# Sch_ECGAcquisitionSystem.net
KiCad netlist of a schematic drawn in Altium Designer
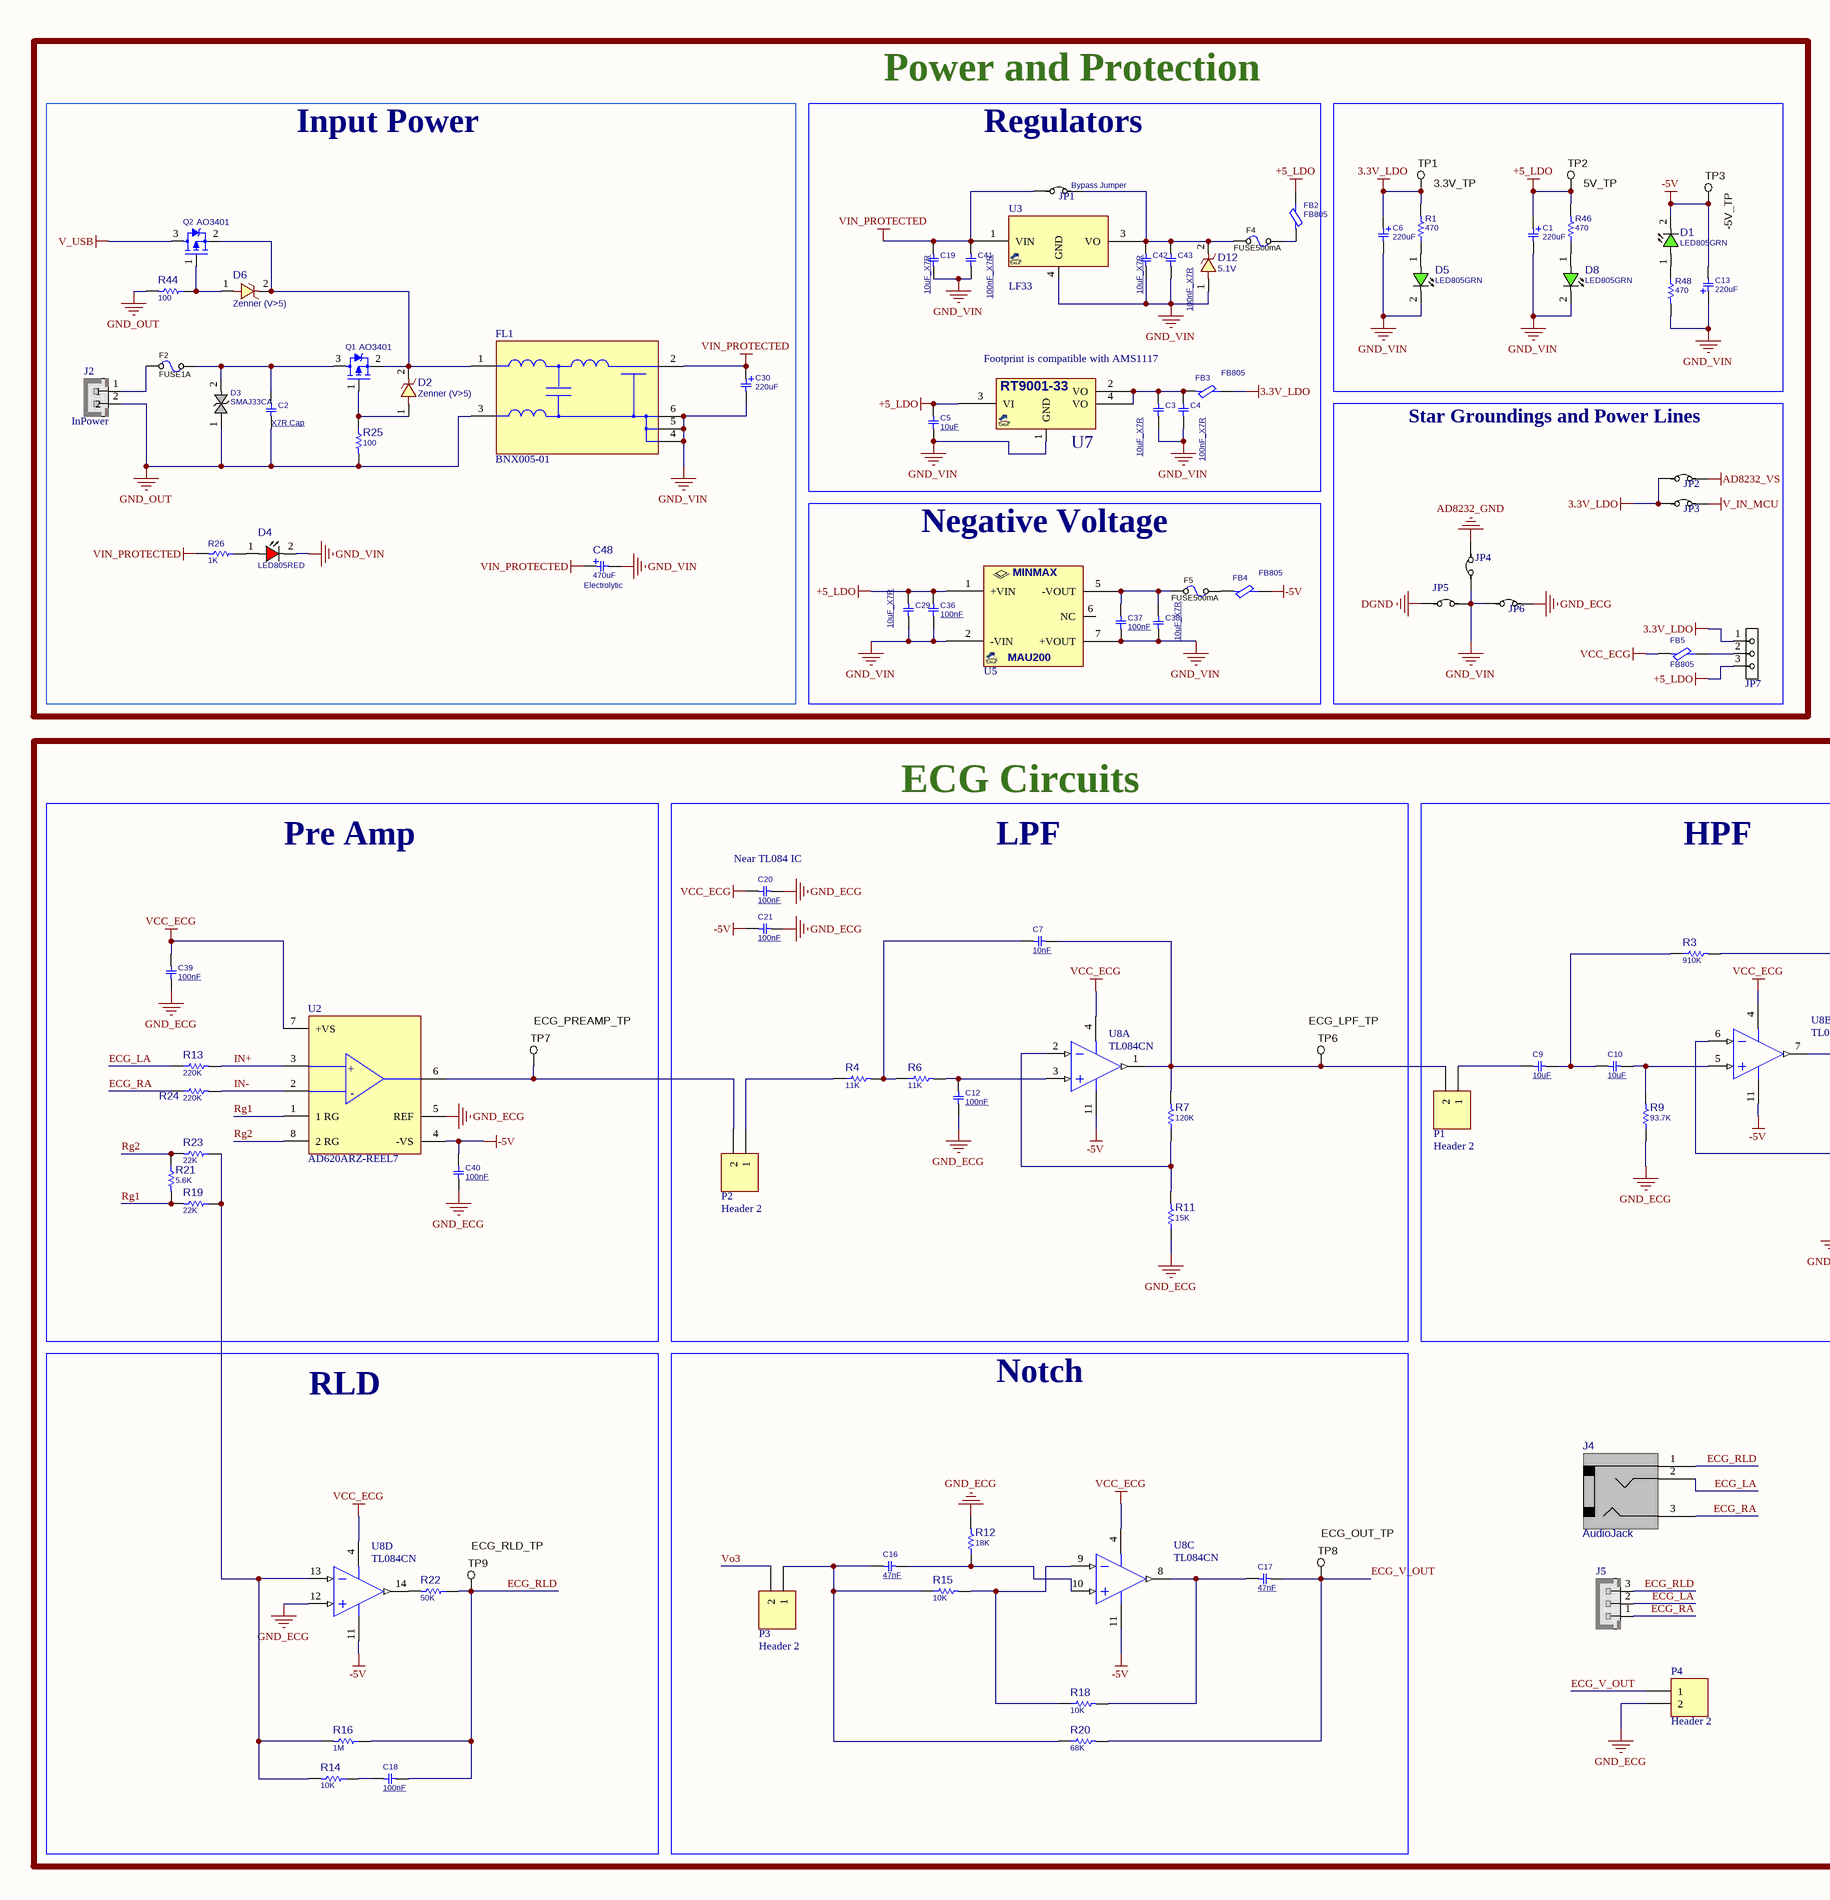
[diagram p0: Sch_ECGAcquisitionSystem.SchDoc, left]
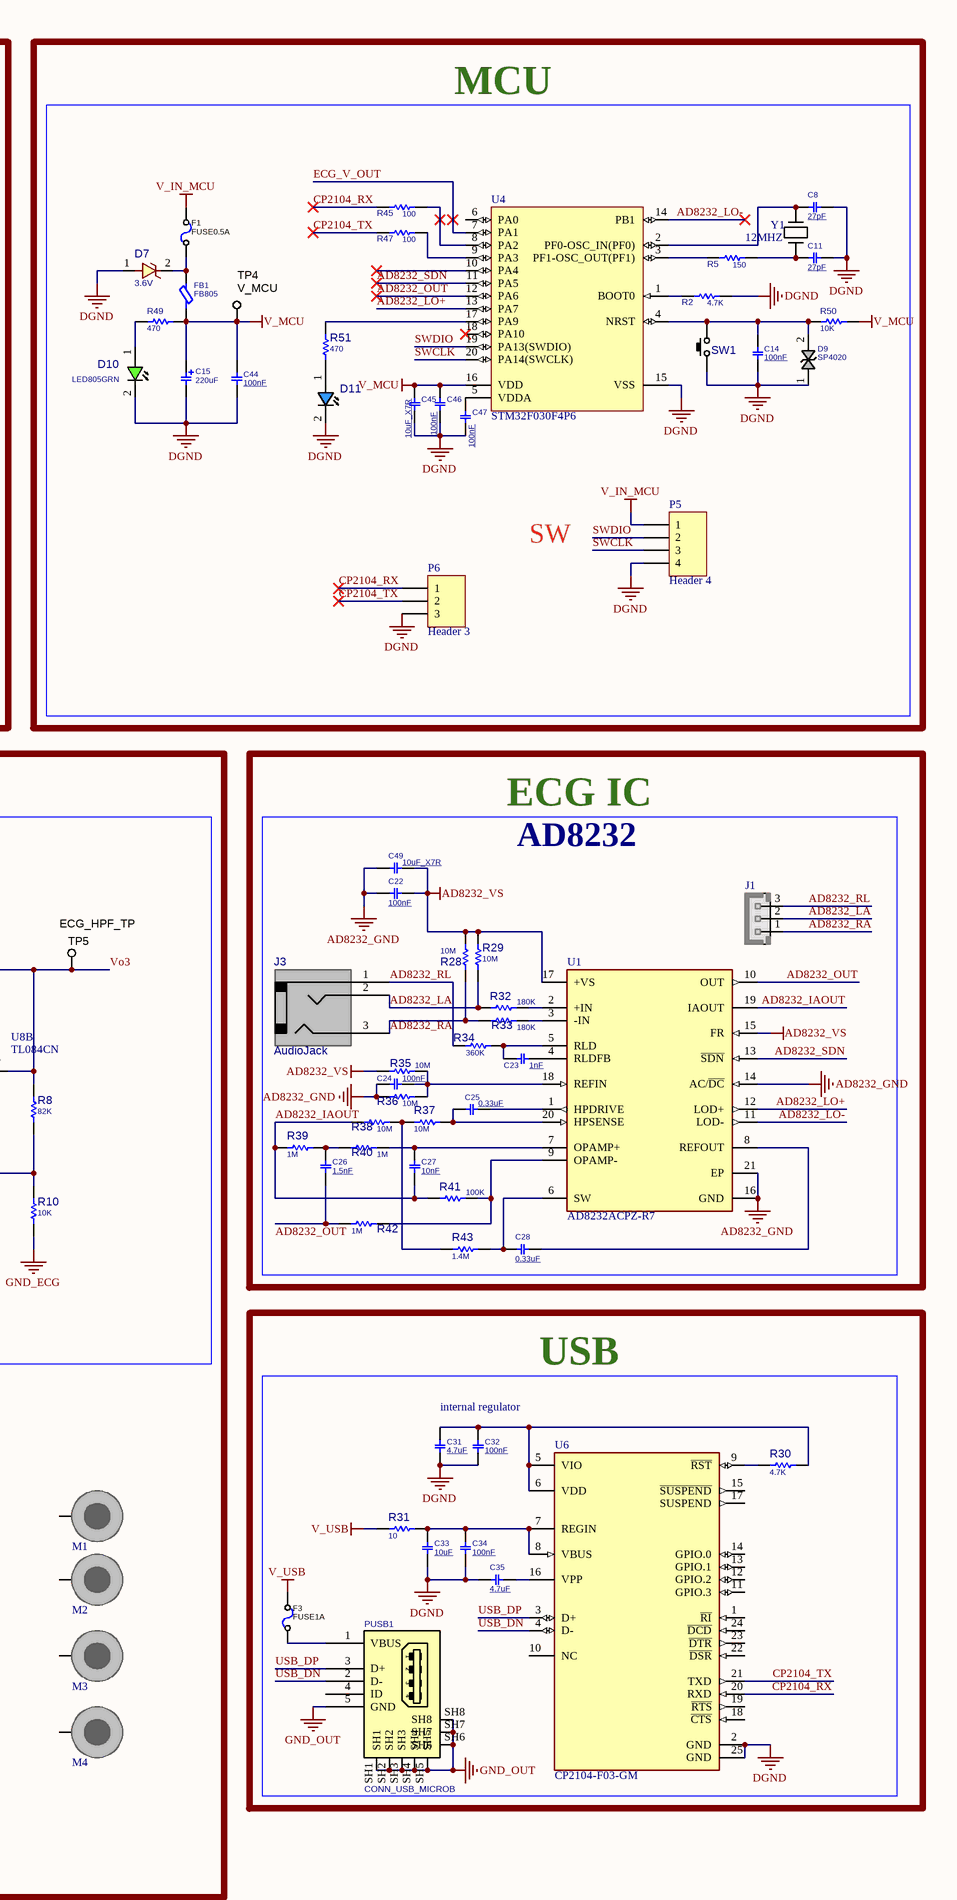
[diagram p1: Sch_ECGAcquisitionSystem.SchDoc, right]

(export (version "E")
  (design (tool "Eeschema 10.0.6"))
  (components
    (comp (ref "C1")
      (value "220uF")
      (footprint "C_TN_7343")
      (description "CAP, SMD, TAN")
      (fields (field (name "MANF") "VISHAY") (field (name "MANF_P#") "T55D227M6R3C0035"))
      (libsource (lib "CapTantal_passive") (part "CAP_SMD_TAN_220uF"))
    )
    (comp (ref "C2")
      (value "X7R Cap")
      (footprint "C0805S")
      (description "CAP, MLCC, -F, -V, MATERIAL, -%, 0201")
      (fields (field (name "MANF_P#") "MANF_PART#"))
      (libsource (lib "passive_smd") (part "CAP_SMD_MLCC_0805"))
    )
    (comp (ref "C3")
      (value "10uF_X7R")
      (footprint "C0805S")
      (description "CAP, MLCC, -F, -V, MATERIAL, -%, 0201")
      (fields (field (name "MANF_P#") "MANF_PART#"))
      (libsource (lib "passive_smd") (part "CAP_SMD_MLCC_0805"))
    )
    (comp (ref "C4")
      (value "100nF_X7R")
      (footprint "C0805S")
      (description "CAP, MLCC, -F, -V, MATERIAL, -%, 0201")
      (fields (field (name "MANF_P#") "MANF_PART#"))
      (libsource (lib "passive_smd") (part "CAP_SMD_MLCC_0805"))
    )
    (comp (ref "C5")
      (value "10uF")
      (footprint "C0805S")
      (description "CAP, MLCC, -F, -V, MATERIAL, -%, 0201")
      (fields (field (name "MANF_P#") "MANF_PART#"))
      (libsource (lib "passive_smd") (part "CAP_SMD_MLCC_0805"))
    )
    (comp (ref "C6")
      (value "220uF")
      (footprint "C_TN_7343")
      (description "CAP, SMD, TAN")
      (fields (field (name "MANF") "VISHAY") (field (name "MANF_P#") "T55D227M6R3C0035"))
      (libsource (lib "CapTantal_passive") (part "CAP_SMD_TAN_220uF"))
    )
    (comp (ref "C7")
      (value "10nF")
      (footprint "C0805S")
      (description "CAP, MLCC, -F, -V, MATERIAL, -%, 0201")
      (fields (field (name "MANF_P#") "MANF_PART#"))
      (libsource (lib "passive_smd") (part "CAP_SMD_MLCC_0805"))
    )
    (comp (ref "C8")
      (value "27pF")
      (footprint "C0805")
      (description "CAP, MLCC, -F, -V, MATERIAL, -%, 0201")
      (fields (field (name "MANF_P#") "MANF_PART#"))
      (libsource (lib "passive_smd") (part "CAP_SMD_MLCC_0805"))
    )
    (comp (ref "C9")
      (value "10uF")
      (footprint "C0805S")
      (description "CAP, MLCC, -F, -V, MATERIAL, -%, 0201")
      (fields (field (name "MANF_P#") "MANF_PART#"))
      (libsource (lib "passive_smd") (part "CAP_SMD_MLCC_0805"))
    )
    (comp (ref "C10")
      (value "10uF")
      (footprint "C0805S")
      (description "CAP, MLCC, -F, -V, MATERIAL, -%, 0201")
      (fields (field (name "MANF_P#") "MANF_PART#"))
      (libsource (lib "passive_smd") (part "CAP_SMD_MLCC_0805"))
    )
    (comp (ref "C11")
      (value "27pF")
      (footprint "C0805")
      (description "CAP, MLCC, -F, -V, MATERIAL, -%, 0201")
      (fields (field (name "MANF_P#") "MANF_PART#"))
      (libsource (lib "passive_smd") (part "CAP_SMD_MLCC_0805"))
    )
    (comp (ref "C12")
      (value "100nF")
      (footprint "C0805S")
      (description "CAP, MLCC, -F, -V, MATERIAL, -%, 0201")
      (fields (field (name "MANF_P#") "MANF_PART#"))
      (libsource (lib "passive_smd") (part "CAP_SMD_MLCC_0805"))
    )
    (comp (ref "C13")
      (value "220uF")
      (footprint "C_TN_7343")
      (description "CAP, SMD, TAN")
      (fields (field (name "MANF") "VISHAY") (field (name "MANF_P#") "T55D227M6R3C0035"))
      (libsource (lib "CapTantal_passive") (part "CAP_SMD_TAN_220uF"))
    )
    (comp (ref "C14")
      (value "100nF")
      (footprint "C0805S")
      (description "CAP, MLCC, -F, -V, MATERIAL, -%, 0201")
      (fields (field (name "MANF_P#") "MANF_PART#"))
      (libsource (lib "passive_smd") (part "CAP_SMD_MLCC_0805"))
    )
    (comp (ref "C15")
      (value "220uF")
      (footprint "C_TN_7343")
      (description "CAP, SMD, TAN")
      (fields (field (name "MANF") "VISHAY") (field (name "MANF_P#") "T55D227M6R3C0035"))
      (libsource (lib "CapTantal_passive") (part "CAP_SMD_TAN_220uF"))
    )
    (comp (ref "C16")
      (value "47nF")
      (footprint "C0805S")
      (description "CAP, MLCC, -F, -V, MATERIAL, -%, 0201")
      (fields (field (name "MANF_P#") "MANF_PART#"))
      (libsource (lib "passive_smd") (part "CAP_SMD_MLCC_0805"))
    )
    (comp (ref "C17")
      (value "47nF")
      (footprint "C0805S")
      (description "CAP, MLCC, -F, -V, MATERIAL, -%, 0201")
      (fields (field (name "MANF_P#") "MANF_PART#"))
      (libsource (lib "passive_smd") (part "CAP_SMD_MLCC_0805"))
    )
    (comp (ref "C18")
      (value "100nF")
      (footprint "C0805S")
      (description "CAP, MLCC, -F, -V, MATERIAL, -%, 0201")
      (fields (field (name "MANF_P#") "MANF_PART#"))
      (libsource (lib "passive_smd") (part "CAP_SMD_MLCC_0805"))
    )
    (comp (ref "C19")
      (value "10uF_X7R")
      (footprint "C0805S")
      (description "CAP, MLCC, -F, -V, MATERIAL, -%, 0201")
      (fields (field (name "MANF_P#") "MANF_PART#"))
      (libsource (lib "passive_smd") (part "CAP_SMD_MLCC_0805"))
    )
    (comp (ref "C20")
      (value "100nF")
      (footprint "C0805S")
      (description "CAP, MLCC, -F, -V, MATERIAL, -%, 0201")
      (fields (field (name "MANF_P#") "MANF_PART#"))
      (libsource (lib "passive_smd") (part "CAP_SMD_MLCC_0805"))
    )
    (comp (ref "C21")
      (value "100nF")
      (footprint "C0805S")
      (description "CAP, MLCC, -F, -V, MATERIAL, -%, 0201")
      (fields (field (name "MANF_P#") "MANF_PART#"))
      (libsource (lib "passive_smd") (part "CAP_SMD_MLCC_0805"))
    )
    (comp (ref "C22")
      (value "100nF")
      (footprint "C0805")
      (description "CAP, MLCC, -F, -V, MATERIAL, -%, 0201")
      (fields (field (name "MANF_P#") "MANF_PART#"))
      (libsource (lib "passive_smd") (part "CAP_SMD_MLCC_0805"))
    )
    (comp (ref "C23")
      (value "1nF")
      (footprint "C0805")
      (description "CAP, MLCC, -F, -V, MATERIAL, -%, 0201")
      (fields (field (name "MANF_P#") "MANF_PART#"))
      (libsource (lib "passive_smd") (part "CAP_SMD_MLCC_0805"))
    )
    (comp (ref "C24")
      (value "100nF")
      (footprint "C0805")
      (description "CAP, MLCC, -F, -V, MATERIAL, -%, 0201")
      (fields (field (name "MANF_P#") "MANF_PART#"))
      (libsource (lib "passive_smd") (part "CAP_SMD_MLCC_0805"))
    )
    (comp (ref "C25")
      (value "0.33uF")
      (footprint "C0805")
      (description "CAP, MLCC, -F, -V, MATERIAL, -%, 0201")
      (fields (field (name "MANF_P#") "MANF_PART#"))
      (libsource (lib "passive_smd") (part "CAP_SMD_MLCC_0805"))
    )
    (comp (ref "C26")
      (value "1.5nF")
      (footprint "C0805")
      (description "CAP, MLCC, -F, -V, MATERIAL, -%, 0201")
      (fields (field (name "MANF_P#") "MANF_PART#"))
      (libsource (lib "passive_smd") (part "CAP_SMD_MLCC_0805"))
    )
    (comp (ref "C27")
      (value "10nF")
      (footprint "C0805")
      (description "CAP, MLCC, -F, -V, MATERIAL, -%, 0201")
      (fields (field (name "MANF_P#") "MANF_PART#"))
      (libsource (lib "passive_smd") (part "CAP_SMD_MLCC_0805"))
    )
    (comp (ref "C28")
      (value "0.33uF")
      (footprint "C0805")
      (description "CAP, MLCC, -F, -V, MATERIAL, -%, 0201")
      (fields (field (name "MANF_P#") "MANF_PART#"))
      (libsource (lib "passive_smd") (part "CAP_SMD_MLCC_0805"))
    )
    (comp (ref "C29")
      (value "10uF_X7R")
      (footprint "C0805S")
      (description "CAP, MLCC, -F, -V, MATERIAL, -%, 0201")
      (fields (field (name "MANF_P#") "MANF_PART#"))
      (libsource (lib "passive_smd") (part "CAP_SMD_MLCC_0805"))
    )
    (comp (ref "C30")
      (value "220uF")
      (footprint "C_TN_7343")
      (description "CAP, SMD, TAN")
      (fields (field (name "MANF") "VISHAY") (field (name "MANF_P#") "T55D227M6R3C0035"))
      (libsource (lib "CapTantal_passive") (part "CAP_SMD_TAN_220uF"))
    )
    (comp (ref "C31")
      (value "4.7uF")
      (footprint "C0805")
      (description "CAP, MLCC, -F, -V, MATERIAL, -%, 0201")
      (fields (field (name "MANF_P#") "MANF_PART#"))
      (libsource (lib "passive_smd") (part "CAP_SMD_MLCC_0805"))
    )
    (comp (ref "C32")
      (value "100nF")
      (footprint "C0805")
      (description "CAP, MLCC, -F, -V, MATERIAL, -%, 0201")
      (fields (field (name "MANF_P#") "MANF_PART#"))
      (libsource (lib "passive_smd") (part "CAP_SMD_MLCC_0805"))
    )
    (comp (ref "C33")
      (value "10uF")
      (footprint "C0805")
      (description "CAP, MLCC, -F, -V, MATERIAL, -%, 0201")
      (fields (field (name "MANF_P#") "MANF_PART#"))
      (libsource (lib "passive_smd") (part "CAP_SMD_MLCC_0805"))
    )
    (comp (ref "C34")
      (value "100nF")
      (footprint "C0805")
      (description "CAP, MLCC, -F, -V, MATERIAL, -%, 0201")
      (fields (field (name "MANF_P#") "MANF_PART#"))
      (libsource (lib "passive_smd") (part "CAP_SMD_MLCC_0805"))
    )
    (comp (ref "C35")
      (value "4.7uF")
      (footprint "C0805")
      (description "CAP, MLCC, -F, -V, MATERIAL, -%, 0201")
      (fields (field (name "MANF_P#") "MANF_PART#"))
      (libsource (lib "passive_smd") (part "CAP_SMD_MLCC_0805"))
    )
    (comp (ref "C36")
      (value "100nF")
      (footprint "C0805S")
      (description "CAP, MLCC, -F, -V, MATERIAL, -%, 0201")
      (fields (field (name "MANF_P#") "MANF_PART#"))
      (libsource (lib "passive_smd") (part "CAP_SMD_MLCC_0805"))
    )
    (comp (ref "C37")
      (value "100nF")
      (footprint "C0805S")
      (description "CAP, MLCC, -F, -V, MATERIAL, -%, 0201")
      (fields (field (name "MANF_P#") "MANF_PART#"))
      (libsource (lib "passive_smd") (part "CAP_SMD_MLCC_0805"))
    )
    (comp (ref "C38")
      (value "10uF_X7R")
      (footprint "C0805S")
      (description "CAP, MLCC, -F, -V, MATERIAL, -%, 0201")
      (fields (field (name "MANF_P#") "MANF_PART#"))
      (libsource (lib "passive_smd") (part "CAP_SMD_MLCC_0805"))
    )
    (comp (ref "C39")
      (value "100nF")
      (footprint "C0805S")
      (description "CAP, MLCC, -F, -V, MATERIAL, -%, 0201")
      (fields (field (name "MANF_P#") "MANF_PART#"))
      (libsource (lib "passive_smd") (part "CAP_SMD_MLCC_0805"))
    )
    (comp (ref "C40")
      (value "100nF")
      (footprint "C0805S")
      (description "CAP, MLCC, -F, -V, MATERIAL, -%, 0201")
      (fields (field (name "MANF_P#") "MANF_PART#"))
      (libsource (lib "passive_smd") (part "CAP_SMD_MLCC_0805"))
    )
    (comp (ref "C41")
      (value "100nF_X7R")
      (footprint "C0805S")
      (description "CAP, MLCC, -F, -V, MATERIAL, -%, 0201")
      (fields (field (name "MANF_P#") "MANF_PART#"))
      (libsource (lib "passive_smd") (part "CAP_SMD_MLCC_0805"))
    )
    (comp (ref "C42")
      (value "10uF_X7R")
      (footprint "C0805S")
      (description "CAP, MLCC, -F, -V, MATERIAL, -%, 0201")
      (fields (field (name "MANF_P#") "MANF_PART#"))
      (libsource (lib "passive_smd") (part "CAP_SMD_MLCC_0805"))
    )
    (comp (ref "C43")
      (value "100nF_X7R")
      (footprint "C0805S")
      (description "CAP, MLCC, -F, -V, MATERIAL, -%, 0201")
      (fields (field (name "MANF_P#") "MANF_PART#"))
      (libsource (lib "passive_smd") (part "CAP_SMD_MLCC_0805"))
    )
    (comp (ref "C44")
      (value "100nF")
      (footprint "C0805")
      (description "CAP, MLCC, -F, -V, MATERIAL, -%, 0201")
      (fields (field (name "MANF_P#") "MANF_PART#"))
      (libsource (lib "passive_smd") (part "CAP_SMD_MLCC_0805"))
    )
    (comp (ref "C45")
      (value "10uF_X7R")
      (footprint "C0805S")
      (description "CAP, MLCC, -F, -V, MATERIAL, -%, 0201")
      (fields (field (name "MANF_P#") "MANF_PART#"))
      (libsource (lib "passive_smd") (part "CAP_SMD_MLCC_0805"))
    )
    (comp (ref "C46")
      (value "100nF")
      (footprint "C0805")
      (description "CAP, MLCC, -F, -V, MATERIAL, -%, 0201")
      (fields (field (name "MANF_P#") "MANF_PART#"))
      (libsource (lib "passive_smd") (part "CAP_SMD_MLCC_0805"))
    )
    (comp (ref "C47")
      (value "100nF")
      (footprint "C0805")
      (description "CAP, MLCC, -F, -V, MATERIAL, -%, 0201")
      (fields (field (name "MANF_P#") "MANF_PART#"))
      (libsource (lib "passive_smd") (part "CAP_SMD_MLCC_0805"))
    )
    (comp (ref "C48")
      (value "Electrolytic")
      (footprint "C_EL_6_8")
      (description "CAP, SMD, ELEC,")
      (fields
        (field (name "MANF_P#") "16SVPE180M")
        (field (name "MANF") "Panasonic")
        (field (name "ALTIUM_VALUE") "470uF")
      )
      (libsource (lib "CapElect_passive") (part "CAP_SMD_EL_180u16V"))
    )
    (comp (ref "C49")
      (value "10uF_X7R")
      (footprint "C0805S")
      (description "CAP, MLCC, -F, -V, MATERIAL, -%, 0201")
      (fields (field (name "MANF_P#") "MANF_PART#"))
      (libsource (lib "passive_smd") (part "CAP_SMD_MLCC_0805"))
    )
    (comp (ref "D1")
      (value "LED805GRN")
      (footprint "LED0805GRN")
      (description "LED, SMD, 0805, GREEN")
      (libsource (lib "led(diode)") (part "LED_SMD_0805_GRN"))
    )
    (comp (ref "D2")
      (value "Zenner (V>5)")
      (footprint "D_SOD123W")
      (description "DIODE, ZENER, 1W, 5.1V")
      (fields (field (name "MANF") "Diodes") (field (name "MANF_P#") "BZT52HC5V1WF-7"))
      (libsource (lib "diode") (part "DIODE_SMD_ZENER_BZT52HC5V1"))
    )
    (comp (ref "D3")
      (value "SMAJ33CA")
      (footprint "D_SMA")
      (description "TVS, ESD PROTECT, Bidirectional")
      (fields (field (name "MANF_P#") "SMAJ12CA") (field (name "MANF") "Littelfuse"))
      (libsource (lib "protect_tvs_esd_fuse") (part "TVS_SMAJ12CA"))
    )
    (comp (ref "D4")
      (value "LED805RED")
      (footprint "LED0805RED")
      (description "LED, SMD, 0805, RED")
      (fields (field (name "MANF") "MANF") (field (name "MANF_P#") "MANF_PART#"))
      (libsource (lib "led(diode)") (part "LED_SMD_0805_RED"))
    )
    (comp (ref "D5")
      (value "LED805GRN")
      (footprint "LED0805GRN")
      (description "LED, SMD, 0805, GREEN")
      (libsource (lib "led(diode)") (part "LED_SMD_0805_GRN"))
    )
    (comp (ref "D6")
      (value "Zenner (V>5)")
      (footprint "D_SOD123W")
      (description "DIODE, ZENER, 1W, 5.1V")
      (fields (field (name "MANF") "Diodes") (field (name "MANF_P#") "BZT52HC5V1WF-7"))
      (libsource (lib "diode") (part "DIODE_SMD_ZENER_BZT52HC5V1"))
    )
    (comp (ref "D7")
      (value "3.6V")
      (footprint "D_SOD123W")
      (description "DIODE, ZENER, 1W, 5.1V")
      (fields (field (name "MANF") "Diodes") (field (name "MANF_P#") "BZT52HC5V1WF-7"))
      (libsource (lib "diode") (part "DIODE_SMD_ZENER_BZT52HC5V1"))
    )
    (comp (ref "D8")
      (value "LED805GRN")
      (footprint "LED0805GRN")
      (description "LED, SMD, 0805, GREEN")
      (libsource (lib "led(diode)") (part "LED_SMD_0805_GRN"))
    )
    (comp (ref "D9")
      (value "SP4020")
      (footprint "D_SOD323")
      (description "TVS, ESD PROTECT,")
      (fields (field (name "MANF_P#") "PESD1IVN27-AX") (field (name "MANF") "NXP"))
      (libsource (lib "protect_tvs_esd_fuse") (part "TVS_PESD1IVN27"))
    )
    (comp (ref "D10")
      (value "LED805GRN")
      (footprint "LED0805GRN")
      (description "LED, SMD, 0805, GREEN")
      (libsource (lib "led(diode)") (part "LED_SMD_0805_GRN"))
    )
    (comp (ref "D11")
      (value "~")
      (footprint "LED0805BLU")
      (description "LED, SMD, 0805, BLUE")
      (fields (field (name "MANF") "MANF") (field (name "MANF_P#") "MANF_PART#"))
      (libsource (lib "led(diode)") (part "LED_SMD_0805_BLU"))
    )
    (comp (ref "D12")
      (value "5.1V")
      (footprint "D_SOD123W")
      (description "DIODE, ZENER, 1W, 5.1V")
      (fields (field (name "MANF") "Diodes") (field (name "MANF_P#") "BZT52HC5V1WF-7"))
      (libsource (lib "diode") (part "DIODE_SMD_ZENER_BZT52HC5V1"))
    )
    (comp (ref "F1")
      (value "FUSE0.5A")
      (footprint "F1206")
      (description "Fuse, 160mA, 63VDC, 1206, SMD, Fast Acting")
      (fields (field (name "MANF") "Holly Fuse") (field (name "MANF_P#") "12T-0160L"))
      (libsource (lib "protect_tvs_esd_fuse") (part "FUSE_160mA_1206"))
    )
    (comp (ref "F2")
      (value "FUSE1A")
      (footprint "F1206")
      (description "Fuse, 160mA, 63VDC, 1206, SMD, Fast Acting")
      (fields (field (name "MANF") "Holly Fuse") (field (name "MANF_P#") "12T-0160L"))
      (libsource (lib "protect_tvs_esd_fuse") (part "FUSE_160mA_1206"))
    )
    (comp (ref "F3")
      (value "FUSE1A")
      (footprint "F1206")
      (description "Fuse, 160mA, 63VDC, 1206, SMD, Fast Acting")
      (fields (field (name "MANF") "Holly Fuse") (field (name "MANF_P#") "12T-0160L"))
      (libsource (lib "protect_tvs_esd_fuse") (part "FUSE_160mA_1206"))
    )
    (comp (ref "F4")
      (value "FUSE500mA")
      (footprint "F0805")
      (description "Fuse, 500mA, 32VDC, 0805, SMD, Fast Acting")
      (fields (field (name "MANF") "MANF") (field (name "MANF_P#") "MANF_PART#"))
      (libsource (lib "protect_tvs_esd_fuse") (part "FUSE_500mA_0805_FAST"))
    )
    (comp (ref "F5")
      (value "FUSE500mA")
      (footprint "F0805")
      (description "Fuse, 500mA, 32VDC, 0805, SMD, Fast Acting")
      (fields (field (name "MANF") "MANF") (field (name "MANF_P#") "MANF_PART#"))
      (libsource (lib "protect_tvs_esd_fuse") (part "FUSE_500mA_0805_FAST"))
    )
    (comp (ref "FB1")
      (value "FB805")
      (footprint "L0805")
      (description "FERRITE_Bead, 0805, 2A, 50mOhm, 220@100MHz")
      (fields (field (name "MANF") "MURATA") (field (name "MANF_P#") "BLM15AG121SN1D"))
      (libsource (lib "emi_filter") (part "FBEAD_SMD_BLM21PG221"))
    )
    (comp (ref "FB2")
      (value "FB805")
      (footprint "L0805")
      (description "FERRITE_Bead, 0805, 2A, 50mOhm, 220@100MHz")
      (fields (field (name "MANF") "MURATA") (field (name "MANF_P#") "BLM15AG121SN1D"))
      (libsource (lib "emi_filter") (part "FBEAD_SMD_BLM21PG221"))
    )
    (comp (ref "FB3")
      (value "FB805")
      (footprint "L0805")
      (description "FERRITE_Bead, 0805, 2A, 50mOhm, 220@100MHz")
      (fields (field (name "MANF") "MURATA") (field (name "MANF_P#") "BLM15AG121SN1D"))
      (libsource (lib "emi_filter") (part "FBEAD_SMD_BLM21PG221"))
    )
    (comp (ref "FB4")
      (value "FB805")
      (footprint "L0805")
      (description "FERRITE_Bead, 0805, 2A, 50mOhm, 220@100MHz")
      (fields (field (name "MANF") "MURATA") (field (name "MANF_P#") "BLM15AG121SN1D"))
      (libsource (lib "emi_filter") (part "FBEAD_SMD_BLM21PG221"))
    )
    (comp (ref "FB5")
      (value "FB805")
      (footprint "L0805")
      (description "FERRITE_Bead, 0805, 2A, 50mOhm, 220@100MHz")
      (fields (field (name "MANF") "MURATA") (field (name "MANF_P#") "BLM15AG121SN1D"))
      (libsource (lib "emi_filter") (part "FBEAD_SMD_BLM21PG221"))
    )
    (comp (ref "FL1")
      (value "BNX005-01")
      (footprint "FP-BNX_L12MM5_W11MM5_T13M-MFG")
      (description "FILTER LC TH")
      (libsource (lib "Altium Content Vault") (part "de100375f5adcbdc36456263c7e2ed8"))
    )
    (comp (ref "J1")
      (value "HHDR_3")
      (footprint "XH_3")
      (description "JST-XH pitch: 2.5mm")
      (libsource (lib "Miscellaneous Connectors") (part "XH_3"))
    )
    (comp (ref "J2")
      (value "InPower")
      (footprint "XH_2")
      (description "JST-XH pitch: 2.5mm")
      (libsource (lib "Miscellaneous Connectors") (part "XH_2"))
    )
    (comp (ref "J3")
      (value "AudioJack")
      (footprint "JCKAS_STX3500")
      (description "Jack, Audio, Stereo, 3.5mm, RA, SMD")
      (fields (field (name "MANF") "Kycon") (field (name "MANF_P#") "STX-3500-3NTR"))
      (libsource (lib "conn_jackAV") (part "JACKA3.5SMD_STX-3500-3"))
    )
    (comp (ref "J4")
      (value "AudioJack")
      (footprint "JCKAS_STX3500")
      (description "Jack, Audio, Stereo, 3.5mm, RA, SMD")
      (fields (field (name "MANF") "Kycon") (field (name "MANF_P#") "STX-3500-3NTR"))
      (libsource (lib "conn_jackAV") (part "JACKA3.5SMD_STX-3500-3"))
    )
    (comp (ref "J5")
      (value "HHDR_3")
      (footprint "XH_3")
      (description "JST-XH pitch: 2.5mm")
      (libsource (lib "Miscellaneous Connectors") (part "XH_3"))
    )
    (comp (ref "JP1")
      (value "Bypass Jumper")
      (footprint "JP_40X50")
      (description "JUMPER, HEADER 2PIN")
      (fields (field (name "MANF") "MANF") (field (name "MANF_P#") "MANF_P#"))
      (libsource (lib "test-tp_jumper") (part "JUMPER_SOLDER"))
    )
    (comp (ref "JP2")
      (value "~")
      (footprint "JP_40X50")
      (description "JUMPER, HEADER 2PIN")
      (fields (field (name "MANF") "MANF") (field (name "MANF_P#") "MANF_P#"))
      (libsource (lib "test-tp_jumper") (part "JUMPER_SOLDER"))
    )
    (comp (ref "JP3")
      (value "~")
      (footprint "JP_40X50")
      (description "JUMPER, HEADER 2PIN")
      (fields (field (name "MANF") "MANF") (field (name "MANF_P#") "MANF_P#"))
      (libsource (lib "test-tp_jumper") (part "JUMPER_SOLDER"))
    )
    (comp (ref "JP4")
      (value "~")
      (footprint "JP_40X50")
      (description "JUMPER, HEADER 2PIN")
      (fields (field (name "MANF") "MANF") (field (name "MANF_P#") "MANF_P#"))
      (libsource (lib "test-tp_jumper") (part "JUMPER_SOLDER"))
    )
    (comp (ref "JP5")
      (value "~")
      (footprint "JP_40X50")
      (description "JUMPER, HEADER 2PIN")
      (fields (field (name "MANF") "MANF") (field (name "MANF_P#") "MANF_P#"))
      (libsource (lib "test-tp_jumper") (part "JUMPER_SOLDER"))
    )
    (comp (ref "JP6")
      (value "~")
      (footprint "JP_40X50")
      (description "JUMPER, HEADER 2PIN")
      (fields (field (name "MANF") "MANF") (field (name "MANF_P#") "MANF_P#"))
      (libsource (lib "test-tp_jumper") (part "JUMPER_SOLDER"))
    )
    (comp (ref "JP7")
      (value "JMPHDR3PIN")
      (footprint "JP_3")
      (description "JUMPER, HEADER 3PIN")
      (fields (field (name "MANF") "MANF") (field (name "MANF_P#") "MANF_P#"))
      (libsource (lib "test-tp_jumper") (part "JUMPER_HDR_3P"))
    )
    (comp (ref "M1")
      (value "DNP/MH")
      (footprint "SCMH_M3")
      (description "SCREW mouting, M3, 3.0mm diameter and 6.0mm PanHead")
      (libsource (lib "mech_mountingHole") (part "SCMH_M3"))
    )
    (comp (ref "M2")
      (value "DNP/MH")
      (footprint "SCMH_M3")
      (description "SCREW mouting, M3, 3.0mm diameter and 6.0mm PanHead")
      (libsource (lib "mech_mountingHole") (part "SCMH_M3"))
    )
    (comp (ref "M3")
      (value "DNP/MH")
      (footprint "SCMH_M3")
      (description "SCREW mouting, M3, 3.0mm diameter and 6.0mm PanHead")
      (libsource (lib "mech_mountingHole") (part "SCMH_M3"))
    )
    (comp (ref "M4")
      (value "DNP/MH")
      (footprint "SCMH_M3")
      (description "SCREW mouting, M3, 3.0mm diameter and 6.0mm PanHead")
      (libsource (lib "mech_mountingHole") (part "SCMH_M3"))
    )
    (comp (ref "P1")
      (value "Header 2")
      (footprint "HDR1X2")
      (description "Header, 2-Pin")
      (fields (field (name "PUBLISHER") "Altium Limited"))
      (libsource (lib "Miscellaneous Connectors") (part "Header 2"))
    )
    (comp (ref "P2")
      (value "Header 2")
      (footprint "HDR1X2")
      (description "Header, 2-Pin")
      (fields (field (name "PUBLISHER") "Altium Limited"))
      (libsource (lib "Miscellaneous Connectors") (part "Header 2"))
    )
    (comp (ref "P3")
      (value "Header 2")
      (footprint "HDR1X2")
      (description "Header, 2-Pin")
      (fields (field (name "PUBLISHER") "Altium Limited"))
      (libsource (lib "Miscellaneous Connectors") (part "Header 2"))
    )
    (comp (ref "P4")
      (value "Header 2")
      (footprint "HDR1X2")
      (description "Header, 2-Pin")
      (fields (field (name "PUBLISHER") "Altium Limited"))
      (libsource (lib "") (part "Header 2_1"))
    )
    (comp (ref "P5")
      (value "Header 4")
      (footprint "HDR1X4")
      (description "Header, 4-Pin")
      (fields (field (name "PUBLISHER") "Altium Limited"))
      (libsource (lib "Miscellaneous Connectors") (part "Header 4"))
    )
    (comp (ref "P6")
      (value "Header 3")
      (footprint "HDR1X3")
      (description "Header, 3-Pin")
      (fields (field (name "PUBLISHER") "Altium Limited"))
      (libsource (lib "Miscellaneous Connectors") (part "Header 3"))
    )
    (comp (ref "PUSB1")
      (value "CONN_USB_MICROB")
      (footprint "USB_MICRO_B_BM_SHS")
      (description "CONN, USB, MICRO B, R/A, SMD, BOTTOM MOUNT")
      (fields (field (name "MANF_P#") "47346-0001") (field (name "MANF") "Molex"))
      (libsource (lib "conn_usb") (part "CONN_USB_MICRO_B_BM_SHS"))
    )
    (comp (ref "Q1")
      (value "AO3401")
      (footprint "SOT23_3")
      (description "MOSFET P-CH AO3401 SMD SOT-23 3P")
      (fields (field (name "MANF") "ALPHA & OMEGA"))
      (libsource (lib "transistor_fet") (part "MOSP_AO3401_SOT23"))
    )
    (comp (ref "Q2")
      (value "AO3401")
      (footprint "SOT23_3")
      (description "MOSFET P-CH AO3401 SMD SOT-23 3P")
      (fields (field (name "MANF") "ALPHA & OMEGA"))
      (libsource (lib "transistor_fet") (part "MOSP_AO3401_SOT23"))
    )
    (comp (ref "R1")
      (value "470")
      (footprint "R0805S")
      (description "RESISTOR, SMD")
      (libsource (lib "passive_smd") (part "RES_SMD"))
    )
    (comp (ref "R2")
      (value "4.7K")
      (footprint "R0805S")
      (description "RESISTOR, SMD")
      (libsource (lib "passive_smd") (part "RES_SMD"))
    )
    (comp (ref "R3")
      (value "910K")
      (footprint "R0805")
      (description "RESISTOR, SMD")
      (libsource (lib "passive_smd") (part "RES_SMD_0805"))
    )
    (comp (ref "R4")
      (value "11K")
      (footprint "R0805")
      (description "RESISTOR, SMD")
      (libsource (lib "passive_smd") (part "RES_SMD_0805"))
    )
    (comp (ref "R5")
      (value "150")
      (footprint "R0805S")
      (description "RESISTOR, SMD")
      (libsource (lib "passive_smd") (part "RES_SMD"))
    )
    (comp (ref "R6")
      (value "11K")
      (footprint "R0805")
      (description "RESISTOR, SMD")
      (libsource (lib "passive_smd") (part "RES_SMD_0805"))
    )
    (comp (ref "R7")
      (value "120K")
      (footprint "R0805")
      (description "RESISTOR, SMD")
      (libsource (lib "passive_smd") (part "RES_SMD_0805"))
    )
    (comp (ref "R8")
      (value "82K")
      (footprint "R0805")
      (description "RESISTOR, SMD")
      (libsource (lib "passive_smd") (part "RES_SMD_0805"))
    )
    (comp (ref "R9")
      (value "93.7K")
      (footprint "R0805")
      (description "RESISTOR, SMD")
      (libsource (lib "passive_smd") (part "RES_SMD_0805"))
    )
    (comp (ref "R10")
      (value "10K")
      (footprint "R0805")
      (description "RESISTOR, SMD")
      (libsource (lib "passive_smd") (part "RES_SMD_0805"))
    )
    (comp (ref "R11")
      (value "15K")
      (footprint "R0805")
      (description "RESISTOR, SMD")
      (libsource (lib "passive_smd") (part "RES_SMD_0805"))
    )
    (comp (ref "R12")
      (value "18K")
      (footprint "R0805")
      (description "RESISTOR, SMD")
      (libsource (lib "passive_smd") (part "RES_SMD_0805"))
    )
    (comp (ref "R13")
      (value "220K")
      (footprint "R0805")
      (description "RESISTOR, SMD")
      (libsource (lib "passive_smd") (part "RES_SMD_0805"))
    )
    (comp (ref "R14")
      (value "10K")
      (footprint "R0805")
      (description "RESISTOR, SMD")
      (libsource (lib "passive_smd") (part "RES_SMD_0805"))
    )
    (comp (ref "R15")
      (value "10K")
      (footprint "R0805")
      (description "RESISTOR, SMD")
      (libsource (lib "passive_smd") (part "RES_SMD_0805"))
    )
    (comp (ref "R16")
      (value "1M")
      (footprint "R0805")
      (description "RESISTOR, SMD")
      (libsource (lib "passive_smd") (part "RES_SMD_0805"))
    )
    (comp (ref "R18")
      (value "10K")
      (footprint "R0805")
      (description "RESISTOR, SMD")
      (libsource (lib "passive_smd") (part "RES_SMD_0805"))
    )
    (comp (ref "R19")
      (value "22K")
      (footprint "R0805")
      (description "RESISTOR, SMD")
      (libsource (lib "passive_smd") (part "RES_SMD_0805"))
    )
    (comp (ref "R20")
      (value "68K")
      (footprint "R0805")
      (description "RESISTOR, SMD")
      (libsource (lib "passive_smd") (part "RES_SMD_0805"))
    )
    (comp (ref "R21")
      (value "5.6K")
      (footprint "R0805")
      (description "RESISTOR, SMD")
      (libsource (lib "passive_smd") (part "RES_SMD_0805"))
    )
    (comp (ref "R22")
      (value "50K")
      (footprint "R0805")
      (description "RESISTOR, SMD")
      (libsource (lib "passive_smd") (part "RES_SMD_0805"))
    )
    (comp (ref "R23")
      (value "22K")
      (footprint "R0805")
      (description "RESISTOR, SMD")
      (libsource (lib "passive_smd") (part "RES_SMD_0805"))
    )
    (comp (ref "R24")
      (value "220K")
      (footprint "R0805")
      (description "RESISTOR, SMD")
      (libsource (lib "passive_smd") (part "RES_SMD_0805"))
    )
    (comp (ref "R25")
      (value "100")
      (footprint "R0805S")
      (description "RESISTOR, SMD")
      (libsource (lib "passive_smd") (part "RES_SMD"))
    )
    (comp (ref "R26")
      (value "1K")
      (footprint "R0805S")
      (description "RESISTOR, SMD")
      (libsource (lib "passive_smd") (part "RES_SMD"))
    )
    (comp (ref "R28")
      (value "10M")
      (footprint "R0805")
      (description "RESISTOR, SMD")
      (libsource (lib "passive_smd") (part "RES_SMD_0805"))
    )
    (comp (ref "R29")
      (value "10M")
      (footprint "R0805")
      (description "RESISTOR, SMD")
      (libsource (lib "passive_smd") (part "RES_SMD_0805"))
    )
    (comp (ref "R30")
      (value "4.7K")
      (footprint "R0805")
      (description "RESISTOR, SMD")
      (libsource (lib "passive_smd") (part "RES_SMD_0805"))
    )
    (comp (ref "R31")
      (value "10")
      (footprint "R0805")
      (description "RESISTOR, SMD")
      (libsource (lib "passive_smd") (part "RES_SMD_0805"))
    )
    (comp (ref "R32")
      (value "180K")
      (footprint "R0805")
      (description "RESISTOR, SMD")
      (libsource (lib "passive_smd") (part "RES_SMD_0805"))
    )
    (comp (ref "R33")
      (value "180K")
      (footprint "R0805")
      (description "RESISTOR, SMD")
      (libsource (lib "passive_smd") (part "RES_SMD_0805"))
    )
    (comp (ref "R34")
      (value "360K")
      (footprint "R0805")
      (description "RESISTOR, SMD")
      (libsource (lib "passive_smd") (part "RES_SMD_0805"))
    )
    (comp (ref "R35")
      (value "10M")
      (footprint "R0805")
      (description "RESISTOR, SMD")
      (libsource (lib "passive_smd") (part "RES_SMD_0805"))
    )
    (comp (ref "R36")
      (value "10M")
      (footprint "R0805")
      (description "RESISTOR, SMD")
      (libsource (lib "passive_smd") (part "RES_SMD_0805"))
    )
    (comp (ref "R37")
      (value "10M")
      (footprint "R0805")
      (description "RESISTOR, SMD")
      (libsource (lib "passive_smd") (part "RES_SMD_0805"))
    )
    (comp (ref "R38")
      (value "10M")
      (footprint "R0805")
      (description "RESISTOR, SMD")
      (libsource (lib "passive_smd") (part "RES_SMD_0805"))
    )
    (comp (ref "R39")
      (value "1M")
      (footprint "R0805")
      (description "RESISTOR, SMD")
      (libsource (lib "passive_smd") (part "RES_SMD_0805"))
    )
    (comp (ref "R40")
      (value "1M")
      (footprint "R0805")
      (description "RESISTOR, SMD")
      (libsource (lib "passive_smd") (part "RES_SMD_0805"))
    )
    (comp (ref "R41")
      (value "100K")
      (footprint "R0805")
      (description "RESISTOR, SMD")
      (libsource (lib "passive_smd") (part "RES_SMD_0805"))
    )
    (comp (ref "R42")
      (value "1M")
      (footprint "R0805")
      (description "RESISTOR, SMD")
      (libsource (lib "passive_smd") (part "RES_SMD_0805"))
    )
    (comp (ref "R43")
      (value "1.4M")
      (footprint "R0805")
      (description "RESISTOR, SMD")
      (libsource (lib "passive_smd") (part "RES_SMD_0805"))
    )
    (comp (ref "R44")
      (value "100")
      (footprint "R0805S")
      (description "RESISTOR, SMD")
      (libsource (lib "passive_smd") (part "RES_SMD"))
    )
    (comp (ref "R45")
      (value "100")
      (footprint "R0805S")
      (description "RESISTOR, SMD")
      (libsource (lib "passive_smd") (part "RES_SMD"))
    )
    (comp (ref "R46")
      (value "470")
      (footprint "R0805S")
      (description "RESISTOR, SMD")
      (libsource (lib "passive_smd") (part "RES_SMD"))
    )
    (comp (ref "R47")
      (value "100")
      (footprint "R0805S")
      (description "RESISTOR, SMD")
      (libsource (lib "passive_smd") (part "RES_SMD"))
    )
    (comp (ref "R48")
      (value "470")
      (footprint "R0805S")
      (description "RESISTOR, SMD")
      (libsource (lib "passive_smd") (part "RES_SMD"))
    )
    (comp (ref "R49")
      (value "470")
      (footprint "R0805S")
      (description "RESISTOR, SMD")
      (libsource (lib "passive_smd") (part "RES_SMD"))
    )
    (comp (ref "R50")
      (value "10K")
      (footprint "R0805S")
      (description "RESISTOR, SMD")
      (libsource (lib "passive_smd") (part "RES_SMD"))
    )
    (comp (ref "R51")
      (value "470")
      (footprint "R0805S")
      (description "RESISTOR, SMD")
      (libsource (lib "passive_smd") (part "RES_SMD"))
    )
    (comp (ref "SW1")
      (value "PUSHBUTTON")
      (footprint "SWPBS_SPST_6X3X5")
      (description "SWITCH, PUSH BUTTON, TACTILE, SMD, SPST, 6X3.5X4.3mm")
      (fields (field (name "MANF") "Panasonic") (field (name "MANF_P#") "EVQ-PNF04M"))
      (libsource (lib "switch_tact_PUSHB") (part "SWPBS_SPST_6X3X4"))
    )
    (comp (ref "TP1")
      (value "3.3V_TP")
      (footprint "TPTHD_C_BLK2")
      (description "TEST POINT")
      (fields (field (name "MANF") "MANF") (field (name "MANF_P#") "MANF_P#"))
      (libsource (lib "test-tp_jumper") (part "TESTPOINT_BIG_BLK2"))
    )
    (comp (ref "TP2")
      (value "5V_TP")
      (footprint "TPTHD_C_BLK2")
      (description "TEST POINT")
      (fields (field (name "MANF") "MANF") (field (name "MANF_P#") "MANF_P#"))
      (libsource (lib "test-tp_jumper") (part "TESTPOINT_BIG_BLK2"))
    )
    (comp (ref "TP3")
      (value "-5V_TP")
      (footprint "TPTHD_C_BLK2")
      (description "TEST POINT")
      (fields (field (name "MANF") "MANF") (field (name "MANF_P#") "MANF_P#"))
      (libsource (lib "test-tp_jumper") (part "TESTPOINT_BIG_BLK2"))
    )
    (comp (ref "TP4")
      (value "V_MCU")
      (footprint "TPSMD_S1")
      (description "TEST POINT")
      (fields (field (name "MANF") "MANF") (field (name "MANF_P#") "MANF_P#"))
      (libsource (lib "test-tp_jumper") (part "TESTPOINT_SMD"))
    )
    (comp (ref "TP5")
      (value "ECG_HPF_TP")
      (footprint "TPTHD_C_BLK2")
      (description "TEST POINT")
      (fields (field (name "MANF") "MANF") (field (name "MANF_P#") "MANF_P#"))
      (libsource (lib "test-tp_jumper") (part "TESTPOINT_BIG_BLK2"))
    )
    (comp (ref "TP6")
      (value "ECG_LPF_TP")
      (footprint "TPTHD_C_BLK2")
      (description "TEST POINT")
      (fields (field (name "MANF") "MANF") (field (name "MANF_P#") "MANF_P#"))
      (libsource (lib "test-tp_jumper") (part "TESTPOINT_BIG_BLK2"))
    )
    (comp (ref "TP7")
      (value "ECG_PREAMP_TP")
      (footprint "TPTHD_C_BLK2")
      (description "TEST POINT")
      (fields (field (name "MANF") "MANF") (field (name "MANF_P#") "MANF_P#"))
      (libsource (lib "test-tp_jumper") (part "TESTPOINT_BIG_BLK2"))
    )
    (comp (ref "TP8")
      (value "ECG_OUT_TP")
      (footprint "TPTHD_C_BLK2")
      (description "TEST POINT")
      (fields (field (name "MANF") "MANF") (field (name "MANF_P#") "MANF_P#"))
      (libsource (lib "test-tp_jumper") (part "TESTPOINT_BIG_BLK2"))
    )
    (comp (ref "TP9")
      (value "ECG_RLD_TP")
      (footprint "TPTHD_C_BLK2")
      (description "TEST POINT")
      (fields (field (name "MANF") "MANF") (field (name "MANF_P#") "MANF_P#"))
      (libsource (lib "test-tp_jumper") (part "TESTPOINT_BIG_BLK2"))
    )
    (comp (ref "U1")
      (value "AD8232ACPZ-R7")
      (footprint "FP-CP-20-8-IPC_C")
      (description "IC ECG FRONT END 20LFCSP")
      (libsource (lib "Altium Content Vault") (part "1c637333606c892ebbd82e67949bb2a"))
    )
    (comp (ref "U2")
      (value "AD620ARZ-REEL7")
      (footprint "FP-R-8-IPC_B")
      (description "IC INST AMP 1 CIRCUIT 8SOIC")
      (libsource (lib "Altium Content Vault") (part "0450056d8b8a4b7768ba406df0ba6bf"))
    )
    (comp (ref "U3")
      (value "LF33")
      (footprint "DPAK_3")
      (description "REG, Linear, LDO0.45V, 0.5A, TO-252")
      (fields (field (name "MANF") "ST"))
      (libsource (lib "pwr_reg_linear") (part "VREG_LFXX_TO252"))
    )
    (comp (ref "U4")
      (value "STM32F030F4P6")
      (footprint "STM-TSSOP20_L")
      (libsource (lib "Altium Content Vault") (part "MC-ARM-STM32F030-IL20"))
    )
    (comp (ref "U5")
      (value "MAU202")
      (footprint "MINMAX_MAU200")
      (description "DC-DC Converter, Isolated, 1W")
      (fields (field (name "MANF") "MINMAX"))
      (libsource (lib "module_dc2dc_iso") (part "MAU202"))
    )
    (comp (ref "U6")
      (value "CP2104-F03-GM")
      (footprint "FP-CP2104-F03-GM-MFG")
      (description "IC SGL USB-TO-UART BRIDGE 24QFN")
      (libsource (lib "Altium Content Vault") (part "36aa9e967c7f1036f799a443da3d357"))
    )
    (comp (ref "U7")
      (value "RT9001-33")
      (footprint "SOT223_4")
      (description "(Footprint is compatible with AMS1117) REG, Linear, LDO0.58V, 0.6A, 3.3V FIXED, SOT223")
      (fields (field (name "MANF_P#") "RT9001-33GG") (field (name "MANF") "RICHTEK"))
      (libsource (lib "pwr_reg_linear_LDO_highPSRR") (part "VREG_RT9001-33_SOT223"))
    )
    (comp (ref "U8")
      (value "TL084CN")
      (footprint "N0014A")
      (description "JFET-Input Operational Amplifier, 7 to 36 V, 0 to 70 degC, 14-pin DIP (N14), Pb-Free (RoHS)")
      (fields (field (name "MANUFACTURER") "Texas Instruments"))
      (libsource (lib "Altium Content Vault") (part "TI-TLXX4X_MC3403-X14"))
    )
    (comp (ref "Y1")
      (value "12MHZ")
      (footprint "XTL_2_11X5")
      (description "SMD CRYSTAL")
      (libsource (lib "vh_altium_library") (part "CRYSTAL-GENERIC"))
    )
  )
  (nets
    (net (code "1") (name "+5_LDO") (class "Default")
      (node (ref "C1") (pin "1") (pinfunction "1_1") (pintype "passive"))
      (node (ref "C29") (pin "2") (pinfunction "2_2") (pintype "passive"))
      (node (ref "C36") (pin "2") (pinfunction "2_2") (pintype "passive"))
      (node (ref "C5") (pin "2") (pinfunction "2_2") (pintype "passive"))
      (node (ref "FB2") (pin "2") (pinfunction "2_2") (pintype "passive"))
      (node (ref "JP7") (pin "3") (pinfunction "3_3") (pintype "passive"))
      (node (ref "R46") (pin "2") (pinfunction "2_2") (pintype "passive"))
      (node (ref "TP2") (pin "1") (pinfunction "1_1") (pintype "passive"))
      (node (ref "U5") (pin "1") (pinfunction "+VIN_1") (pintype "passive"))
      (node (ref "U7") (pin "3") (pinfunction "VI_3") (pintype "passive"))
    )
    (net (code "2") (name "-5V") (class "Default")
      (node (ref "C13") (pin "2") (pinfunction "2_2") (pintype "passive"))
      (node (ref "C21") (pin "2") (pinfunction "2_2") (pintype "passive"))
      (node (ref "C40") (pin "1") (pinfunction "1_1") (pintype "passive"))
      (node (ref "D1") (pin "2") (pinfunction "CATHODE_2") (pintype "passive"))
      (node (ref "FB4") (pin "2") (pinfunction "2_2") (pintype "passive"))
      (node (ref "TP3") (pin "1") (pinfunction "1_1") (pintype "passive"))
      (node (ref "U2") (pin "4") (pinfunction "-VS_4") (pintype "power_in"))
      (node (ref "U8") (pin "11") (pinfunction "VCC-_11") (pintype "power_in"))
    )
    (net (code "3") (name "/AD8232_IAOUT") (class "Default")
      (node (ref "C27") (pin "2") (pinfunction "2_2") (pintype "passive"))
      (node (ref "R38") (pin "1") (pinfunction "1_1") (pintype "passive"))
      (node (ref "R39") (pin "1") (pinfunction "1_1") (pintype "passive"))
      (node (ref "R41") (pin "1") (pinfunction "1_1") (pintype "passive"))
      (node (ref "U1") (pin "19") (pinfunction "IAOUT_19") (pintype "passive"))
    )
    (net (code "4") (name "/AD8232_LA") (class "Default")
      (node (ref "J1") (pin "2") (pinfunction "2_2") (pintype "passive"))
      (node (ref "J3") (pin "2") (pinfunction "TIP_2") (pintype "passive"))
      (node (ref "R29") (pin "2") (pinfunction "2_2") (pintype "passive"))
      (node (ref "R32") (pin "2") (pinfunction "2_2") (pintype "passive"))
    )
    (net (code "5") (name "/AD8232_LO+") (class "Default")
      (node (ref "U1") (pin "12") (pinfunction "LOD+_12") (pintype "output"))
      (node (ref "U4") (pin "13") (pinfunction "PA7_13") (pintype "bidirectional"))
    )
    (net (code "6") (name "/AD8232_LO-") (class "Default")
      (node (ref "U1") (pin "11") (pinfunction "LOD-_11") (pintype "output"))
      (node (ref "U4") (pin "14") (pinfunction "PB1_14") (pintype "bidirectional"))
    )
    (net (code "7") (name "/AD8232_OUT") (class "Default")
      (node (ref "C26") (pin "2") (pinfunction "2_2") (pintype "passive"))
      (node (ref "R42") (pin "1") (pinfunction "1_1") (pintype "passive"))
      (node (ref "U1") (pin "10") (pinfunction "OUT_10") (pintype "output"))
      (node (ref "U4") (pin "12") (pinfunction "PA6_12") (pintype "bidirectional"))
    )
    (net (code "8") (name "/AD8232_RA") (class "Default")
      (node (ref "J1") (pin "1") (pinfunction "1_1") (pintype "passive"))
      (node (ref "J3") (pin "3") (pinfunction "RING_3") (pintype "passive"))
      (node (ref "R28") (pin "2") (pinfunction "2_2") (pintype "passive"))
      (node (ref "R33") (pin "2") (pinfunction "2_2") (pintype "passive"))
    )
    (net (code "9") (name "/AD8232_RL") (class "Default")
      (node (ref "J1") (pin "3") (pinfunction "3_3") (pintype "passive"))
      (node (ref "J3") (pin "1") (pinfunction "SHIELD_1") (pintype "passive"))
      (node (ref "R34") (pin "2") (pinfunction "2_2") (pintype "passive"))
    )
    (net (code "10") (name "/AD8232_SDN") (class "Default")
      (node (ref "U1") (pin "13") (pinfunction "~{SDN}_13") (pintype "input"))
      (node (ref "U4") (pin "11") (pinfunction "PA5_11") (pintype "bidirectional"))
    )
    (net (code "11") (name "/CP2104_RX") (class "Default")
      (node (ref "P6") (pin "1") (pinfunction "1_1") (pintype "passive"))
      (node (ref "R45") (pin "1") (pinfunction "1_1") (pintype "passive"))
      (node (ref "U6") (pin "20") (pinfunction "RXD_20") (pintype "input"))
    )
    (net (code "12") (name "/CP2104_TX") (class "Default")
      (node (ref "P6") (pin "2") (pinfunction "2_2") (pintype "passive"))
      (node (ref "R47") (pin "1") (pinfunction "1_1") (pintype "passive"))
      (node (ref "U6") (pin "21") (pinfunction "TXD_21") (pintype "output"))
    )
    (net (code "13") (name "/ECG_LA") (class "Default")
      (node (ref "J4") (pin "2") (pinfunction "TIP_2") (pintype "passive"))
      (node (ref "J5") (pin "2") (pinfunction "2_2") (pintype "passive"))
      (node (ref "R13") (pin "1") (pinfunction "1_1") (pintype "passive"))
    )
    (net (code "14") (name "/ECG_RA") (class "Default")
      (node (ref "J4") (pin "3") (pinfunction "RING_3") (pintype "passive"))
      (node (ref "J5") (pin "1") (pinfunction "1_1") (pintype "passive"))
      (node (ref "R24") (pin "1") (pinfunction "1_1") (pintype "passive"))
    )
    (net (code "15") (name "/ECG_RLD") (class "Default")
      (node (ref "C18") (pin "1") (pinfunction "1_1") (pintype "passive"))
      (node (ref "J4") (pin "1") (pinfunction "SHIELD_1") (pintype "passive"))
      (node (ref "J5") (pin "3") (pinfunction "3_3") (pintype "passive"))
      (node (ref "R16") (pin "1") (pinfunction "1_1") (pintype "passive"))
      (node (ref "R22") (pin "1") (pinfunction "1_1") (pintype "passive"))
      (node (ref "TP9") (pin "1") (pinfunction "1_1") (pintype "passive"))
    )
    (net (code "16") (name "/ECG_V_OUT") (class "Default")
      (node (ref "C17") (pin "1") (pinfunction "1_1") (pintype "passive"))
      (node (ref "P4") (pin "1") (pinfunction "1_1") (pintype "passive"))
      (node (ref "R20") (pin "2") (pinfunction "2_2") (pintype "passive"))
      (node (ref "TP8") (pin "1") (pinfunction "1_1") (pintype "passive"))
      (node (ref "U4") (pin "7") (pinfunction "PA1_7") (pintype "bidirectional"))
    )
    (net (code "17") (name "/IN+") (class "Default")
      (node (ref "R13") (pin "2") (pinfunction "2_2") (pintype "passive"))
      (node (ref "U2") (pin "3") (pinfunction "+IN_3") (pintype "tri_state"))
    )
    (net (code "18") (name "/IN-") (class "Default")
      (node (ref "R24") (pin "2") (pinfunction "2_2") (pintype "passive"))
      (node (ref "U2") (pin "2") (pinfunction "-IN_2") (pintype "tri_state"))
    )
    (net (code "19") (name "/Rg1") (class "Default")
      (node (ref "R19") (pin "2") (pinfunction "2_2") (pintype "passive"))
      (node (ref "R21") (pin "2") (pinfunction "2_2") (pintype "passive"))
      (node (ref "U2") (pin "1") (pinfunction "1_RG_1") (pintype "passive"))
    )
    (net (code "20") (name "/Rg2") (class "Default")
      (node (ref "R21") (pin "1") (pinfunction "1_1") (pintype "passive"))
      (node (ref "R23") (pin "2") (pinfunction "2_2") (pintype "passive"))
      (node (ref "U2") (pin "8") (pinfunction "2_RG_8") (pintype "passive"))
    )
    (net (code "21") (name "/SWCLK") (class "Default")
      (node (ref "P5") (pin "3") (pinfunction "3_3") (pintype "passive"))
      (node (ref "U4") (pin "20") (pinfunction "PA14(SWCLK)_20") (pintype "bidirectional"))
    )
    (net (code "22") (name "/SWDIO") (class "Default")
      (node (ref "P5") (pin "2") (pinfunction "2_2") (pintype "passive"))
      (node (ref "U4") (pin "19") (pinfunction "PA13(SWDIO)_19") (pintype "bidirectional"))
    )
    (net (code "23") (name "/USB_DN") (class "Default")
      (node (ref "PUSB1") (pin "2") (pinfunction "D-_2") (pintype "passive"))
      (node (ref "U6") (pin "4") (pinfunction "D-_4") (pintype "bidirectional"))
    )
    (net (code "24") (name "/USB_DP") (class "Default")
      (node (ref "PUSB1") (pin "3") (pinfunction "D+_3") (pintype "passive"))
      (node (ref "U6") (pin "3") (pinfunction "D+_3") (pintype "bidirectional"))
    )
    (net (code "25") (name "/Vo3") (class "Default")
      (node (ref "P3") (pin "2") (pinfunction "2_2") (pintype "passive"))
      (node (ref "R3") (pin "2") (pinfunction "2_2") (pintype "passive"))
      (node (ref "R8") (pin "2") (pinfunction "2_2") (pintype "passive"))
      (node (ref "TP5") (pin "1") (pinfunction "1_1") (pintype "passive"))
      (node (ref "U8") (pin "7") (pinfunction "OUT2_7") (pintype "output"))
    )
    (net (code "26") (name "3.3V_LDO") (class "Default")
      (node (ref "C6") (pin "1") (pinfunction "1_1") (pintype "passive"))
      (node (ref "FB3") (pin "2") (pinfunction "2_2") (pintype "passive"))
      (node (ref "JP2") (pin "1") (pinfunction "1_1") (pintype "passive"))
      (node (ref "JP3") (pin "1") (pinfunction "1_1") (pintype "passive"))
      (node (ref "JP7") (pin "1") (pinfunction "1_1") (pintype "passive"))
      (node (ref "R1") (pin "2") (pinfunction "2_2") (pintype "passive"))
      (node (ref "TP1") (pin "1") (pinfunction "1_1") (pintype "passive"))
    )
    (net (code "27") (name "AD8232_GND") (class "Default")
      (node (ref "C22") (pin "1") (pinfunction "1_1") (pintype "passive"))
      (node (ref "C24") (pin "2") (pinfunction "2_2") (pintype "passive"))
      (node (ref "C49") (pin "2") (pinfunction "2_2") (pintype "passive"))
      (node (ref "JP4") (pin "2") (pinfunction "2_2") (pintype "passive"))
      (node (ref "R36") (pin "2") (pinfunction "2_2") (pintype "passive"))
      (node (ref "U1") (pin "14") (pinfunction "AC/~{DC}_14") (pintype "input"))
      (node (ref "U1") (pin "16") (pinfunction "GND_16") (pintype "power_in"))
      (node (ref "U1") (pin "21") (pinfunction "EP_21") (pintype "power_in"))
    )
    (net (code "28") (name "AD8232_VS") (class "Default")
      (node (ref "C22") (pin "2") (pinfunction "2_2") (pintype "passive"))
      (node (ref "C49") (pin "1") (pinfunction "1_1") (pintype "passive"))
      (node (ref "JP2") (pin "2") (pinfunction "2_2") (pintype "passive"))
      (node (ref "R28") (pin "1") (pinfunction "1_1") (pintype "passive"))
      (node (ref "R29") (pin "1") (pinfunction "1_1") (pintype "passive"))
      (node (ref "R35") (pin "2") (pinfunction "2_2") (pintype "passive"))
      (node (ref "U1") (pin "15") (pinfunction "FR_15") (pintype "input"))
      (node (ref "U1") (pin "17") (pinfunction "+VS_17") (pintype "power_in"))
    )
    (net (code "29") (name "DGND") (class "Default")
      (node (ref "C11") (pin "2") (pinfunction "2_2") (pintype "passive"))
      (node (ref "C14") (pin "2") (pinfunction "2_2") (pintype "passive"))
      (node (ref "C15") (pin "2") (pinfunction "2_2") (pintype "passive"))
      (node (ref "C31") (pin "1") (pinfunction "1_1") (pintype "passive"))
      (node (ref "C32") (pin "1") (pinfunction "1_1") (pintype "passive"))
      (node (ref "C33") (pin "1") (pinfunction "1_1") (pintype "passive"))
      (node (ref "C34") (pin "1") (pinfunction "1_1") (pintype "passive"))
      (node (ref "C35") (pin "1") (pinfunction "1_1") (pintype "passive"))
      (node (ref "C44") (pin "2") (pinfunction "2_2") (pintype "passive"))
      (node (ref "C45") (pin "1") (pinfunction "1_1") (pintype "passive"))
      (node (ref "C46") (pin "2") (pinfunction "2_2") (pintype "passive"))
      (node (ref "C47") (pin "2") (pinfunction "2_2") (pintype "passive"))
      (node (ref "C8") (pin "2") (pinfunction "2_2") (pintype "passive"))
      (node (ref "D10") (pin "2") (pinfunction "CATHODE_2") (pintype "passive"))
      (node (ref "D11") (pin "2") (pinfunction "CATHODE_2") (pintype "passive"))
      (node (ref "D7") (pin "1") (pinfunction "1_1") (pintype "passive"))
      (node (ref "D9") (pin "1") (pinfunction "1_1") (pintype "passive"))
      (node (ref "JP5") (pin "1") (pinfunction "1_1") (pintype "passive"))
      (node (ref "P5") (pin "4") (pinfunction "4_4") (pintype "passive"))
      (node (ref "P6") (pin "3") (pinfunction "3_3") (pintype "passive"))
      (node (ref "R2") (pin "2") (pinfunction "2_2") (pintype "passive"))
      (node (ref "SW1") (pin "1") (pinfunction "P1_1") (pintype "passive"))
      (node (ref "U4") (pin "15") (pinfunction "VSS_15") (pintype "power_in"))
      (node (ref "U6") (pin "2") (pinfunction "GND_2") (pintype "power_in"))
      (node (ref "U6") (pin "25") (pinfunction "GND_25") (pintype "power_in"))
    )
    (net (code "30") (name "GND_ECG") (class "Default")
      (node (ref "C12") (pin "2") (pinfunction "2_2") (pintype "passive"))
      (node (ref "C20") (pin "1") (pinfunction "1_1") (pintype "passive"))
      (node (ref "C21") (pin "1") (pinfunction "1_1") (pintype "passive"))
      (node (ref "C39") (pin "1") (pinfunction "1_1") (pintype "passive"))
      (node (ref "C40") (pin "2") (pinfunction "2_2") (pintype "passive"))
      (node (ref "JP6") (pin "2") (pinfunction "2_2") (pintype "passive"))
      (node (ref "P4") (pin "2") (pinfunction "2_2") (pintype "passive"))
      (node (ref "R10") (pin "1") (pinfunction "1_1") (pintype "passive"))
      (node (ref "R11") (pin "1") (pinfunction "1_1") (pintype "passive"))
      (node (ref "R12") (pin "2") (pinfunction "2_2") (pintype "passive"))
      (node (ref "R9") (pin "1") (pinfunction "1_1") (pintype "passive"))
      (node (ref "U2") (pin "5") (pinfunction "REF_5") (pintype "passive"))
      (node (ref "U8") (pin "12") (pinfunction "IN4+_12") (pintype "input"))
    )
    (net (code "31") (name "GND_OUT") (class "Default")
      (node (ref "C2") (pin "2") (pinfunction "2_2") (pintype "passive"))
      (node (ref "D3") (pin "1") (pinfunction "1_1") (pintype "passive"))
      (node (ref "FL1") (pin "3") (pinfunction "PSG_3") (pintype "passive"))
      (node (ref "J2") (pin "2") (pinfunction "2_2") (pintype "passive"))
      (node (ref "PUSB1") (pin "5") (pinfunction "GND_5") (pintype "power_in"))
      (node (ref "PUSB1") (pin "SH1") (pinfunction "SH1_SH1") (pintype "passive"))
      (node (ref "PUSB1") (pin "SH2") (pinfunction "SH2_SH2") (pintype "passive"))
      (node (ref "PUSB1") (pin "SH3") (pinfunction "SH3_SH3") (pintype "passive"))
      (node (ref "PUSB1") (pin "SH4") (pinfunction "SH4_SH4") (pintype "passive"))
      (node (ref "PUSB1") (pin "SH5") (pinfunction "SH5_SH5") (pintype "passive"))
      (node (ref "PUSB1") (pin "SH6") (pinfunction "SH6_SH6") (pintype "passive"))
      (node (ref "PUSB1") (pin "SH7") (pinfunction "SH7_SH7") (pintype "passive"))
      (node (ref "PUSB1") (pin "SH8") (pinfunction "SH8_SH8") (pintype "passive"))
      (node (ref "R25") (pin "2") (pinfunction "2_2") (pintype "passive"))
      (node (ref "R44") (pin "2") (pinfunction "2_2") (pintype "passive"))
    )
    (net (code "32") (name "GND_VIN") (class "Default")
      (node (ref "C1") (pin "2") (pinfunction "2_2") (pintype "passive"))
      (node (ref "C13") (pin "1") (pinfunction "1_1") (pintype "passive"))
      (node (ref "C19") (pin "1") (pinfunction "1_1") (pintype "passive"))
      (node (ref "C29") (pin "1") (pinfunction "1_1") (pintype "passive"))
      (node (ref "C3") (pin "1") (pinfunction "1_1") (pintype "passive"))
      (node (ref "C30") (pin "2") (pinfunction "2_2") (pintype "passive"))
      (node (ref "C36") (pin "1") (pinfunction "1_1") (pintype "passive"))
      (node (ref "C37") (pin "1") (pinfunction "1_1") (pintype "passive"))
      (node (ref "C38") (pin "2") (pinfunction "2_2") (pintype "passive"))
      (node (ref "C4") (pin "1") (pinfunction "1_1") (pintype "passive"))
      (node (ref "C41") (pin "1") (pinfunction "1_1") (pintype "passive"))
      (node (ref "C42") (pin "1") (pinfunction "1_1") (pintype "passive"))
      (node (ref "C43") (pin "1") (pinfunction "1_1") (pintype "passive"))
      (node (ref "C48") (pin "2") (pinfunction "2_2") (pintype "passive"))
      (node (ref "C5") (pin "1") (pinfunction "1_1") (pintype "passive"))
      (node (ref "C6") (pin "2") (pinfunction "2_2") (pintype "passive"))
      (node (ref "D12") (pin "1") (pinfunction "1_1") (pintype "passive"))
      (node (ref "D4") (pin "2") (pinfunction "CATHODE_2") (pintype "passive"))
      (node (ref "D5") (pin "2") (pinfunction "CATHODE_2") (pintype "passive"))
      (node (ref "D8") (pin "2") (pinfunction "CATHODE_2") (pintype "passive"))
      (node (ref "FL1") (pin "4") (pinfunction "CG_4") (pintype "passive"))
      (node (ref "FL1") (pin "5") (pinfunction "CG_5") (pintype "passive"))
      (node (ref "FL1") (pin "6") (pinfunction "CG_6") (pintype "passive"))
      (node (ref "JP4") (pin "1") (pinfunction "1_1") (pintype "passive"))
      (node (ref "JP5") (pin "2") (pinfunction "2_2") (pintype "passive"))
      (node (ref "JP6") (pin "1") (pinfunction "1_1") (pintype "passive"))
      (node (ref "R48") (pin "2") (pinfunction "2_2") (pintype "passive"))
      (node (ref "U3") (pin "4") (pinfunction "GND_4") (pintype "passive"))
      (node (ref "U5") (pin "2") (pinfunction "-VIN_2") (pintype "passive"))
      (node (ref "U5") (pin "7") (pinfunction "+VOUT_7") (pintype "passive"))
      (node (ref "U7") (pin "1") (pinfunction "GND_1") (pintype "passive"))
    )
    (net (code "33") (name "Net-(C3-Pad2)") (class "Default")
      (node (ref "C3") (pin "2") (pinfunction "2_2") (pintype "passive"))
      (node (ref "C4") (pin "2") (pinfunction "2_2") (pintype "passive"))
      (node (ref "FB3") (pin "1") (pinfunction "1_1") (pintype "passive"))
      (node (ref "U7") (pin "2") (pinfunction "VO_2") (pintype "passive"))
      (node (ref "U7") (pin "4") (pinfunction "VO_4") (pintype "passive"))
    )
    (net (code "34") (name "Net-(C7-Pad2)") (class "Default")
      (node (ref "C7") (pin "2") (pinfunction "2_2") (pintype "passive"))
      (node (ref "R4") (pin "2") (pinfunction "2_2") (pintype "passive"))
      (node (ref "R6") (pin "1") (pinfunction "1_1") (pintype "passive"))
    )
    (net (code "35") (name "Net-(C9-Pad2)") (class "Default")
      (node (ref "C9") (pin "2") (pinfunction "2_2") (pintype "passive"))
      (node (ref "P1") (pin "1") (pinfunction "1_1") (pintype "passive"))
    )
    (net (code "36") (name "Net-(C10-Pad2)") (class "Default")
      (node (ref "C10") (pin "2") (pinfunction "2_2") (pintype "passive"))
      (node (ref "C9") (pin "1") (pinfunction "1_1") (pintype "passive"))
      (node (ref "R3") (pin "1") (pinfunction "1_1") (pintype "passive"))
    )
    (net (code "37") (name "Net-(C11-Pad1)") (class "Default")
      (node (ref "C11") (pin "1") (pinfunction "1_1") (pintype "passive"))
      (node (ref "R5") (pin "2") (pinfunction "2_2") (pintype "passive"))
      (node (ref "Y1") (pin "2") (pintype "passive"))
    )
    (net (code "38") (name "Net-(C16-Pad2)") (class "Default")
      (node (ref "C16") (pin "2") (pinfunction "2_2") (pintype "passive"))
      (node (ref "P3") (pin "1") (pinfunction "1_1") (pintype "passive"))
      (node (ref "R15") (pin "1") (pinfunction "1_1") (pintype "passive"))
      (node (ref "R20") (pin "1") (pinfunction "1_1") (pintype "passive"))
    )
    (net (code "39") (name "Net-(C18-Pad2)") (class "Default")
      (node (ref "C18") (pin "2") (pinfunction "2_2") (pintype "passive"))
      (node (ref "R14") (pin "1") (pinfunction "1_1") (pintype "passive"))
    )
    (net (code "40") (name "Net-(C26-Pad1)") (class "Default")
      (node (ref "C26") (pin "1") (pinfunction "1_1") (pintype "passive"))
      (node (ref "R39") (pin "2") (pinfunction "2_2") (pintype "passive"))
      (node (ref "R40") (pin "1") (pinfunction "1_1") (pintype "passive"))
    )
    (net (code "41") (name "Net-(D1-ANODE)") (class "Default")
      (node (ref "D1") (pin "1") (pinfunction "ANODE_1") (pintype "passive"))
      (node (ref "R48") (pin "1") (pinfunction "1_1") (pintype "passive"))
    )
    (net (code "42") (name "Net-(D4-ANODE)") (class "Default")
      (node (ref "D4") (pin "1") (pinfunction "ANODE_1") (pintype "passive"))
      (node (ref "R26") (pin "1") (pinfunction "1_1") (pintype "passive"))
    )
    (net (code "43") (name "Net-(D5-ANODE)") (class "Default")
      (node (ref "D5") (pin "1") (pinfunction "ANODE_1") (pintype "passive"))
      (node (ref "R1") (pin "1") (pinfunction "1_1") (pintype "passive"))
    )
    (net (code "44") (name "Net-(D7-Pad2)") (class "Default")
      (node (ref "D7") (pin "2") (pinfunction "2_2") (pintype "passive"))
      (node (ref "F1") (pin "1") (pinfunction "1_1") (pintype "passive"))
      (node (ref "FB1") (pin "1") (pinfunction "1_1") (pintype "passive"))
    )
    (net (code "45") (name "Net-(D8-ANODE)") (class "Default")
      (node (ref "D8") (pin "1") (pinfunction "ANODE_1") (pintype "passive"))
      (node (ref "R46") (pin "1") (pinfunction "1_1") (pintype "passive"))
    )
    (net (code "46") (name "Net-(D10-ANODE)") (class "Default")
      (node (ref "D10") (pin "1") (pinfunction "ANODE_1") (pintype "passive"))
      (node (ref "R49") (pin "1") (pinfunction "1_1") (pintype "passive"))
    )
    (net (code "47") (name "Net-(D11-ANODE)") (class "Default")
      (node (ref "D11") (pin "1") (pinfunction "ANODE_1") (pintype "passive"))
      (node (ref "R51") (pin "1") (pinfunction "1_1") (pintype "passive"))
    )
    (net (code "48") (name "Net-(F2-Pad1)") (class "Default")
      (node (ref "F2") (pin "1") (pinfunction "1_1") (pintype "passive"))
      (node (ref "J2") (pin "1") (pinfunction "1_1") (pintype "passive"))
    )
    (net (code "49") (name "Net-(F4-Pad2)") (class "Default")
      (node (ref "F4") (pin "2") (pinfunction "2_2") (pintype "passive"))
      (node (ref "FB2") (pin "1") (pinfunction "1_1") (pintype "passive"))
    )
    (net (code "50") (name "Net-(F5-Pad2)") (class "Default")
      (node (ref "F5") (pin "2") (pinfunction "2_2") (pintype "passive"))
      (node (ref "FB4") (pin "1") (pinfunction "1_1") (pintype "passive"))
    )
    (net (code "51") (name "Net-(FB5-Pad2)") (class "Default")
      (node (ref "FB5") (pin "2") (pinfunction "2_2") (pintype "passive"))
      (node (ref "JP7") (pin "2") (pinfunction "2_2") (pintype "passive"))
    )
    (net (code "52") (name "Net-(FL1-B)") (class "Default")
      (node (ref "D2") (pin "2") (pinfunction "2_2") (pintype "passive"))
      (node (ref "D6") (pin "2") (pinfunction "2_2") (pintype "passive"))
      (node (ref "FL1") (pin "1") (pinfunction "B_1") (pintype "passive"))
      (node (ref "Q1") (pin "2") (pinfunction "S_2") (pintype "passive"))
      (node (ref "Q2") (pin "2") (pinfunction "S_2") (pintype "passive"))
    )
    (net (code "53") (name "Net-(P2-Pad1)") (class "Default")
      (node (ref "P2") (pin "1") (pinfunction "1_1") (pintype "passive"))
      (node (ref "R4") (pin "1") (pinfunction "1_1") (pintype "passive"))
    )
    (net (code "54") (name "Net-(PUSB1-VBUS)") (class "Default")
      (node (ref "F3") (pin "1") (pinfunction "1_1") (pintype "passive"))
      (node (ref "PUSB1") (pin "1") (pinfunction "VBUS_1") (pintype "power_in"))
    )
    (net (code "55") (name "Net-(Q1-D)") (class "Default")
      (node (ref "C2") (pin "1") (pinfunction "1_1") (pintype "passive"))
      (node (ref "D3") (pin "2") (pinfunction "2_2") (pintype "passive"))
      (node (ref "F2") (pin "2") (pinfunction "2_2") (pintype "passive"))
      (node (ref "Q1") (pin "3") (pinfunction "D_3") (pintype "passive"))
    )
    (net (code "56") (name "Net-(Q1-G)") (class "Default")
      (node (ref "D2") (pin "1") (pinfunction "1_1") (pintype "passive"))
      (node (ref "Q1") (pin "1") (pinfunction "G_1") (pintype "passive"))
      (node (ref "R25") (pin "1") (pinfunction "1_1") (pintype "passive"))
    )
    (net (code "57") (name "Net-(Q2-G)") (class "Default")
      (node (ref "D6") (pin "1") (pinfunction "1_1") (pintype "passive"))
      (node (ref "Q2") (pin "1") (pinfunction "G_1") (pintype "passive"))
      (node (ref "R44") (pin "1") (pinfunction "1_1") (pintype "passive"))
    )
    (net (code "58") (name "Net-(R37-Pad2)") (class "Default")
      (node (ref "R37") (pin "2") (pinfunction "2_2") (pintype "passive"))
      (node (ref "R38") (pin "2") (pinfunction "2_2") (pintype "passive"))
      (node (ref "R43") (pin "2") (pinfunction "2_2") (pintype "passive"))
    )
    (net (code "59") (name "Net-(SW1-P3)") (class "Default")
      (node (ref "C14") (pin "1") (pinfunction "1_1") (pintype "passive"))
      (node (ref "D9") (pin "2") (pinfunction "2_2") (pintype "passive"))
      (node (ref "R50") (pin "2") (pinfunction "2_2") (pintype "passive"))
      (node (ref "SW1") (pin "2") (pinfunction "P3_2") (pintype "passive"))
      (node (ref "U4") (pin "4") (pinfunction "NRST_4") (pintype "bidirectional"))
    )
    (net (code "60") (name "Net-(U1-+IN)") (class "Default")
      (node (ref "R32") (pin "1") (pinfunction "1_1") (pintype "passive"))
      (node (ref "U1") (pin "2") (pinfunction "+IN_2") (pintype "tri_state"))
    )
    (net (code "61") (name "Net-(U1--IN)") (class "Default")
      (node (ref "R33") (pin "1") (pinfunction "1_1") (pintype "passive"))
      (node (ref "U1") (pin "3") (pinfunction "-IN_3") (pintype "tri_state"))
    )
    (net (code "62") (name "Net-(U1-HPDRIVE)") (class "Default")
      (node (ref "C25") (pin "1") (pinfunction "1_1") (pintype "passive"))
      (node (ref "U1") (pin "1") (pinfunction "HPDRIVE_1") (pintype "output"))
    )
    (net (code "63") (name "Net-(U1-HPSENSE)") (class "Default")
      (node (ref "C25") (pin "2") (pinfunction "2_2") (pintype "passive"))
      (node (ref "R37") (pin "1") (pinfunction "1_1") (pintype "passive"))
      (node (ref "U1") (pin "20") (pinfunction "HPSENSE_20") (pintype "input"))
    )
    (net (code "64") (name "Net-(U1-OPAMP+)") (class "Default")
      (node (ref "C27") (pin "1") (pinfunction "1_1") (pintype "passive"))
      (node (ref "R40") (pin "2") (pinfunction "2_2") (pintype "passive"))
      (node (ref "U1") (pin "7") (pinfunction "OPAMP+_7") (pintype "tri_state"))
    )
    (net (code "65") (name "Net-(U1-OPAMP-)") (class "Default")
      (node (ref "R41") (pin "2") (pinfunction "2_2") (pintype "passive"))
      (node (ref "R42") (pin "2") (pinfunction "2_2") (pintype "passive"))
      (node (ref "U1") (pin "9") (pinfunction "OPAMP-_9") (pintype "tri_state"))
    )
    (net (code "66") (name "Net-(U1-REFIN)") (class "Default")
      (node (ref "C24") (pin "1") (pinfunction "1_1") (pintype "passive"))
      (node (ref "R35") (pin "1") (pinfunction "1_1") (pintype "passive"))
      (node (ref "R36") (pin "1") (pinfunction "1_1") (pintype "passive"))
      (node (ref "U1") (pin "18") (pinfunction "REFIN_18") (pintype "input"))
    )
    (net (code "67") (name "Net-(U1-REFOUT)") (class "Default")
      (node (ref "C28") (pin "2") (pinfunction "2_2") (pintype "passive"))
      (node (ref "U1") (pin "8") (pinfunction "REFOUT_8") (pintype "passive"))
    )
    (net (code "68") (name "Net-(U1-RLD)") (class "Default")
      (node (ref "C23") (pin "1") (pinfunction "1_1") (pintype "passive"))
      (node (ref "R34") (pin "1") (pinfunction "1_1") (pintype "passive"))
      (node (ref "U1") (pin "5") (pinfunction "RLD_5") (pintype "passive"))
    )
    (net (code "69") (name "Net-(U1-RLDFB)") (class "Default")
      (node (ref "C23") (pin "2") (pinfunction "2_2") (pintype "passive"))
      (node (ref "U1") (pin "4") (pinfunction "RLDFB_4") (pintype "passive"))
    )
    (net (code "70") (name "Net-(U1-SW)") (class "Default")
      (node (ref "C28") (pin "1") (pinfunction "1_1") (pintype "passive"))
      (node (ref "R43") (pin "1") (pinfunction "1_1") (pintype "passive"))
      (node (ref "U1") (pin "6") (pinfunction "SW_6") (pintype "passive"))
    )
    (net (code "71") (name "Net-(U2-OUTPUT)") (class "Default")
      (node (ref "P2") (pin "2") (pinfunction "2_2") (pintype "passive"))
      (node (ref "TP7") (pin "1") (pinfunction "1_1") (pintype "passive"))
      (node (ref "U2") (pin "6") (pinfunction "OUTPUT_6") (pintype "passive"))
    )
    (net (code "72") (name "Net-(U3-VO)") (class "Default")
      (node (ref "C42") (pin "2") (pinfunction "2_2") (pintype "passive"))
      (node (ref "C43") (pin "2") (pinfunction "2_2") (pintype "passive"))
      (node (ref "D12") (pin "2") (pinfunction "2_2") (pintype "passive"))
      (node (ref "F4") (pin "1") (pinfunction "1_1") (pintype "passive"))
      (node (ref "JP1") (pin "2") (pinfunction "2_2") (pintype "passive"))
      (node (ref "U3") (pin "3") (pinfunction "VO_3") (pintype "passive"))
    )
    (net (code "73") (name "Net-(U4-BOOT0)") (class "Default")
      (node (ref "R2") (pin "1") (pinfunction "1_1") (pintype "passive"))
      (node (ref "U4") (pin "1") (pinfunction "BOOT0_1") (pintype "input"))
    )
    (net (code "74") (name "Net-(U4-PA2)") (class "Default")
      (node (ref "R45") (pin "2") (pinfunction "2_2") (pintype "passive"))
      (node (ref "U4") (pin "8") (pinfunction "PA2_8") (pintype "bidirectional"))
    )
    (net (code "75") (name "Net-(U4-PA3)") (class "Default")
      (node (ref "R47") (pin "2") (pinfunction "2_2") (pintype "passive"))
      (node (ref "U4") (pin "9") (pinfunction "PA3_9") (pintype "bidirectional"))
    )
    (net (code "76") (name "Net-(U4-PA9)") (class "Default")
      (node (ref "R51") (pin "2") (pinfunction "2_2") (pintype "passive"))
      (node (ref "U4") (pin "17") (pinfunction "PA9_17") (pintype "bidirectional"))
    )
    (net (code "77") (name "Net-(U4-PF0-OSC_IN(PF0))") (class "Default")
      (node (ref "C8") (pin "1") (pinfunction "1_1") (pintype "passive"))
      (node (ref "U4") (pin "2") (pinfunction "PF0-OSC_IN(PF0)_2") (pintype "bidirectional"))
      (node (ref "Y1") (pin "1") (pintype "passive"))
    )
    (net (code "78") (name "Net-(U4-PF1-OSC_OUT(PF1))") (class "Default")
      (node (ref "R5") (pin "1") (pinfunction "1_1") (pintype "passive"))
      (node (ref "U4") (pin "3") (pinfunction "PF1-OSC_OUT(PF1)_3") (pintype "bidirectional"))
    )
    (net (code "79") (name "Net-(U4-VDDA)") (class "Default")
      (node (ref "C47") (pin "1") (pinfunction "1_1") (pintype "passive"))
      (node (ref "U4") (pin "5") (pinfunction "VDDA_5") (pintype "power_in"))
    )
    (net (code "80") (name "Net-(U5--VOUT)") (class "Default")
      (node (ref "C37") (pin "2") (pinfunction "2_2") (pintype "passive"))
      (node (ref "C38") (pin "1") (pinfunction "1_1") (pintype "passive"))
      (node (ref "F5") (pin "1") (pinfunction "1_1") (pintype "passive"))
      (node (ref "U5") (pin "5") (pinfunction "-VOUT_5") (pintype "passive"))
    )
    (net (code "81") (name "Net-(U6-REGIN)") (class "Default")
      (node (ref "C33") (pin "2") (pinfunction "2_2") (pintype "passive"))
      (node (ref "C34") (pin "2") (pinfunction "2_2") (pintype "passive"))
      (node (ref "R31") (pin "1") (pinfunction "1_1") (pintype "passive"))
      (node (ref "U6") (pin "7") (pinfunction "REGIN_7") (pintype "power_in"))
      (node (ref "U6") (pin "8") (pinfunction "VBUS_8") (pintype "input"))
    )
    (net (code "82") (name "Net-(U6-VDD)") (class "Default")
      (node (ref "C31") (pin "2") (pinfunction "2_2") (pintype "passive"))
      (node (ref "C32") (pin "2") (pinfunction "2_2") (pintype "passive"))
      (node (ref "R30") (pin "1") (pinfunction "1_1") (pintype "passive"))
      (node (ref "U6") (pin "5") (pinfunction "VIO_5") (pintype "power_in"))
      (node (ref "U6") (pin "6") (pinfunction "VDD_6") (pintype "power_in"))
    )
    (net (code "83") (name "Net-(U6-VPP)") (class "Default")
      (node (ref "C35") (pin "2") (pinfunction "2_2") (pintype "passive"))
      (node (ref "U6") (pin "16") (pinfunction "VPP_16") (pintype "passive"))
    )
    (net (code "84") (name "Net-(U6-~{RST})") (class "Default")
      (node (ref "R30") (pin "2") (pinfunction "2_2") (pintype "passive"))
      (node (ref "U6") (pin "9") (pinfunction "~{RST}_9") (pintype "bidirectional"))
    )
    (net (code "85") (name "Net-(U8A-IN1+)") (class "Default")
      (node (ref "C12") (pin "1") (pinfunction "1_1") (pintype "passive"))
      (node (ref "R6") (pin "2") (pinfunction "2_2") (pintype "passive"))
      (node (ref "U8") (pin "3") (pinfunction "IN1+_3") (pintype "input"))
    )
    (net (code "86") (name "Net-(U8A-IN1-)") (class "Default")
      (node (ref "R11") (pin "2") (pinfunction "2_2") (pintype "passive"))
      (node (ref "R7") (pin "1") (pinfunction "1_1") (pintype "passive"))
      (node (ref "U8") (pin "2") (pinfunction "IN1-_2") (pintype "input"))
    )
    (net (code "87") (name "Net-(U8A-OUT1)") (class "Default")
      (node (ref "C7") (pin "1") (pinfunction "1_1") (pintype "passive"))
      (node (ref "P1") (pin "2") (pinfunction "2_2") (pintype "passive"))
      (node (ref "R7") (pin "2") (pinfunction "2_2") (pintype "passive"))
      (node (ref "TP6") (pin "1") (pinfunction "1_1") (pintype "passive"))
      (node (ref "U8") (pin "1") (pinfunction "OUT1_1") (pintype "output"))
    )
    (net (code "88") (name "Net-(U8B-IN2+)") (class "Default")
      (node (ref "C10") (pin "1") (pinfunction "1_1") (pintype "passive"))
      (node (ref "R9") (pin "2") (pinfunction "2_2") (pintype "passive"))
      (node (ref "U8") (pin "5") (pinfunction "IN2+_5") (pintype "input"))
    )
    (net (code "89") (name "Net-(U8B-IN2-)") (class "Default")
      (node (ref "R10") (pin "2") (pinfunction "2_2") (pintype "passive"))
      (node (ref "R8") (pin "1") (pinfunction "1_1") (pintype "passive"))
      (node (ref "U8") (pin "6") (pinfunction "IN2-_6") (pintype "input"))
    )
    (net (code "90") (name "Net-(U8C-IN3+)") (class "Default")
      (node (ref "C16") (pin "1") (pinfunction "1_1") (pintype "passive"))
      (node (ref "R12") (pin "1") (pinfunction "1_1") (pintype "passive"))
      (node (ref "U8") (pin "10") (pinfunction "IN3+_10") (pintype "input"))
    )
    (net (code "91") (name "Net-(U8C-IN3-)") (class "Default")
      (node (ref "R15") (pin "2") (pinfunction "2_2") (pintype "passive"))
      (node (ref "R18") (pin "1") (pinfunction "1_1") (pintype "passive"))
      (node (ref "U8") (pin "9") (pinfunction "IN3-_9") (pintype "input"))
    )
    (net (code "92") (name "Net-(U8C-OUT3)") (class "Default")
      (node (ref "C17") (pin "2") (pinfunction "2_2") (pintype "passive"))
      (node (ref "R18") (pin "2") (pinfunction "2_2") (pintype "passive"))
      (node (ref "U8") (pin "8") (pinfunction "OUT3_8") (pintype "output"))
    )
    (net (code "93") (name "Net-(U8D-IN4-)") (class "Default")
      (node (ref "R14") (pin "2") (pinfunction "2_2") (pintype "passive"))
      (node (ref "R16") (pin "2") (pinfunction "2_2") (pintype "passive"))
      (node (ref "R19") (pin "1") (pinfunction "1_1") (pintype "passive"))
      (node (ref "R23") (pin "1") (pinfunction "1_1") (pintype "passive"))
      (node (ref "U8") (pin "13") (pinfunction "IN4-_13") (pintype "input"))
    )
    (net (code "94") (name "Net-(U8D-OUT4)") (class "Default")
      (node (ref "R22") (pin "2") (pinfunction "2_2") (pintype "passive"))
      (node (ref "U8") (pin "14") (pinfunction "OUT4_14") (pintype "output"))
    )
    (net (code "95") (name "VCC_ECG") (class "Default")
      (node (ref "C20") (pin "2") (pinfunction "2_2") (pintype "passive"))
      (node (ref "C39") (pin "2") (pinfunction "2_2") (pintype "passive"))
      (node (ref "FB5") (pin "1") (pinfunction "1_1") (pintype "passive"))
      (node (ref "U2") (pin "7") (pinfunction "+VS_7") (pintype "power_in"))
      (node (ref "U8") (pin "4") (pinfunction "VCC+_4") (pintype "power_in"))
    )
    (net (code "96") (name "VIN_PROTECTED") (class "Default")
      (node (ref "C19") (pin "2") (pinfunction "2_2") (pintype "passive"))
      (node (ref "C30") (pin "1") (pinfunction "1_1") (pintype "passive"))
      (node (ref "C41") (pin "2") (pinfunction "2_2") (pintype "passive"))
      (node (ref "C48") (pin "1") (pinfunction "1_1") (pintype "passive"))
      (node (ref "FL1") (pin "2") (pinfunction "CB_2") (pintype "passive"))
      (node (ref "JP1") (pin "1") (pinfunction "1_1") (pintype "passive"))
      (node (ref "R26") (pin "2") (pinfunction "2_2") (pintype "passive"))
      (node (ref "U3") (pin "1") (pinfunction "VIN_1") (pintype "passive"))
    )
    (net (code "97") (name "V_IN_MCU") (class "Default")
      (node (ref "F1") (pin "2") (pinfunction "2_2") (pintype "passive"))
      (node (ref "JP3") (pin "2") (pinfunction "2_2") (pintype "passive"))
      (node (ref "P5") (pin "1") (pinfunction "1_1") (pintype "passive"))
    )
    (net (code "98") (name "V_MCU") (class "Default")
      (node (ref "C15") (pin "1") (pinfunction "1_1") (pintype "passive"))
      (node (ref "C44") (pin "1") (pinfunction "1_1") (pintype "passive"))
      (node (ref "C45") (pin "2") (pinfunction "2_2") (pintype "passive"))
      (node (ref "C46") (pin "1") (pinfunction "1_1") (pintype "passive"))
      (node (ref "FB1") (pin "2") (pinfunction "2_2") (pintype "passive"))
      (node (ref "R49") (pin "2") (pinfunction "2_2") (pintype "passive"))
      (node (ref "R50") (pin "1") (pinfunction "1_1") (pintype "passive"))
      (node (ref "TP4") (pin "1") (pinfunction "1_1") (pintype "passive"))
      (node (ref "U4") (pin "16") (pinfunction "VDD_16") (pintype "power_in"))
    )
    (net (code "99") (name "V_USB") (class "Default")
      (node (ref "F3") (pin "2") (pinfunction "2_2") (pintype "passive"))
      (node (ref "Q2") (pin "3") (pinfunction "D_3") (pintype "passive"))
      (node (ref "R31") (pin "2") (pinfunction "2_2") (pintype "passive"))
    )
    (net (code "100") (name "unconnected-(M1-Pad1)") (class "Default")
      (node (ref "M1") (pin "1") (pinfunction "1_1") (pintype "passive"))
    )
    (net (code "101") (name "unconnected-(M2-Pad1)") (class "Default")
      (node (ref "M2") (pin "1") (pinfunction "1_1") (pintype "passive"))
    )
    (net (code "102") (name "unconnected-(M3-Pad1)") (class "Default")
      (node (ref "M3") (pin "1") (pinfunction "1_1") (pintype "passive"))
    )
    (net (code "103") (name "unconnected-(M4-Pad1)") (class "Default")
      (node (ref "M4") (pin "1") (pinfunction "1_1") (pintype "passive"))
    )
    (net (code "104") (name "unconnected-(PUSB1-ID-Pad4)") (class "Default")
      (node (ref "PUSB1") (pin "4") (pinfunction "ID_4") (pintype "power_in"))
    )
    (net (code "105") (name "unconnected-(U4-PA0-Pad6)") (class "Default")
      (node (ref "U4") (pin "6") (pinfunction "PA0_6") (pintype "bidirectional"))
    )
    (net (code "106") (name "unconnected-(U4-PA4-Pad10)") (class "Default")
      (node (ref "U4") (pin "10") (pinfunction "PA4_10") (pintype "bidirectional+no_connect"))
    )
    (net (code "107") (name "unconnected-(U4-PA10-Pad18)") (class "Default")
      (node (ref "U4") (pin "18") (pinfunction "PA10_18") (pintype "bidirectional+no_connect"))
    )
    (net (code "108") (name "unconnected-(U5-NC-Pad6)") (class "Default")
      (node (ref "U5") (pin "6") (pinfunction "NC_6") (pintype "passive"))
    )
    (net (code "109") (name "unconnected-(U6-GPIO.0-Pad14)") (class "Default")
      (node (ref "U6") (pin "14") (pinfunction "GPIO.0_14") (pintype "bidirectional"))
    )
    (net (code "110") (name "unconnected-(U6-GPIO.1-Pad13)") (class "Default")
      (node (ref "U6") (pin "13") (pinfunction "GPIO.1_13") (pintype "bidirectional"))
    )
    (net (code "111") (name "unconnected-(U6-GPIO.2-Pad12)") (class "Default")
      (node (ref "U6") (pin "12") (pinfunction "GPIO.2_12") (pintype "bidirectional"))
    )
    (net (code "112") (name "unconnected-(U6-GPIO.3-Pad11)") (class "Default")
      (node (ref "U6") (pin "11") (pinfunction "GPIO.3_11") (pintype "bidirectional"))
    )
    (net (code "113") (name "unconnected-(U6-NC-Pad10)") (class "Default")
      (node (ref "U6") (pin "10") (pinfunction "NC_10") (pintype "passive"))
    )
    (net (code "114") (name "unconnected-(U6-SUSPEND-Pad17)") (class "Default")
      (node (ref "U6") (pin "17") (pinfunction "SUSPEND_17") (pintype "output"))
    )
    (net (code "115") (name "unconnected-(U6-~{CTS}-Pad18)") (class "Default")
      (node (ref "U6") (pin "18") (pinfunction "~{CTS}_18") (pintype "input"))
    )
    (net (code "116") (name "unconnected-(U6-~{DCD}-Pad24)") (class "Default")
      (node (ref "U6") (pin "24") (pinfunction "~{DCD}_24") (pintype "input"))
    )
    (net (code "117") (name "unconnected-(U6-~{DSR}-Pad22)") (class "Default")
      (node (ref "U6") (pin "22") (pinfunction "~{DSR}_22") (pintype "input"))
    )
    (net (code "118") (name "unconnected-(U6-~{DTR}-Pad23)") (class "Default")
      (node (ref "U6") (pin "23") (pinfunction "~{DTR}_23") (pintype "output"))
    )
    (net (code "119") (name "unconnected-(U6-~{RI}-Pad1)") (class "Default")
      (node (ref "U6") (pin "1") (pinfunction "~{RI}_1") (pintype "input"))
    )
    (net (code "120") (name "unconnected-(U6-~{RTS}-Pad19)") (class "Default")
      (node (ref "U6") (pin "19") (pinfunction "~{RTS}_19") (pintype "output"))
    )
    (net (code "121") (name "unconnected-(U6-~{SUSPEND}-Pad15)") (class "Default")
      (node (ref "U6") (pin "15") (pinfunction "~{SUSPEND}_15") (pintype "output"))
    )
  )
)
